# M8650D_cpld.net
KiCad netlist of a schematic drawn in EAGLE
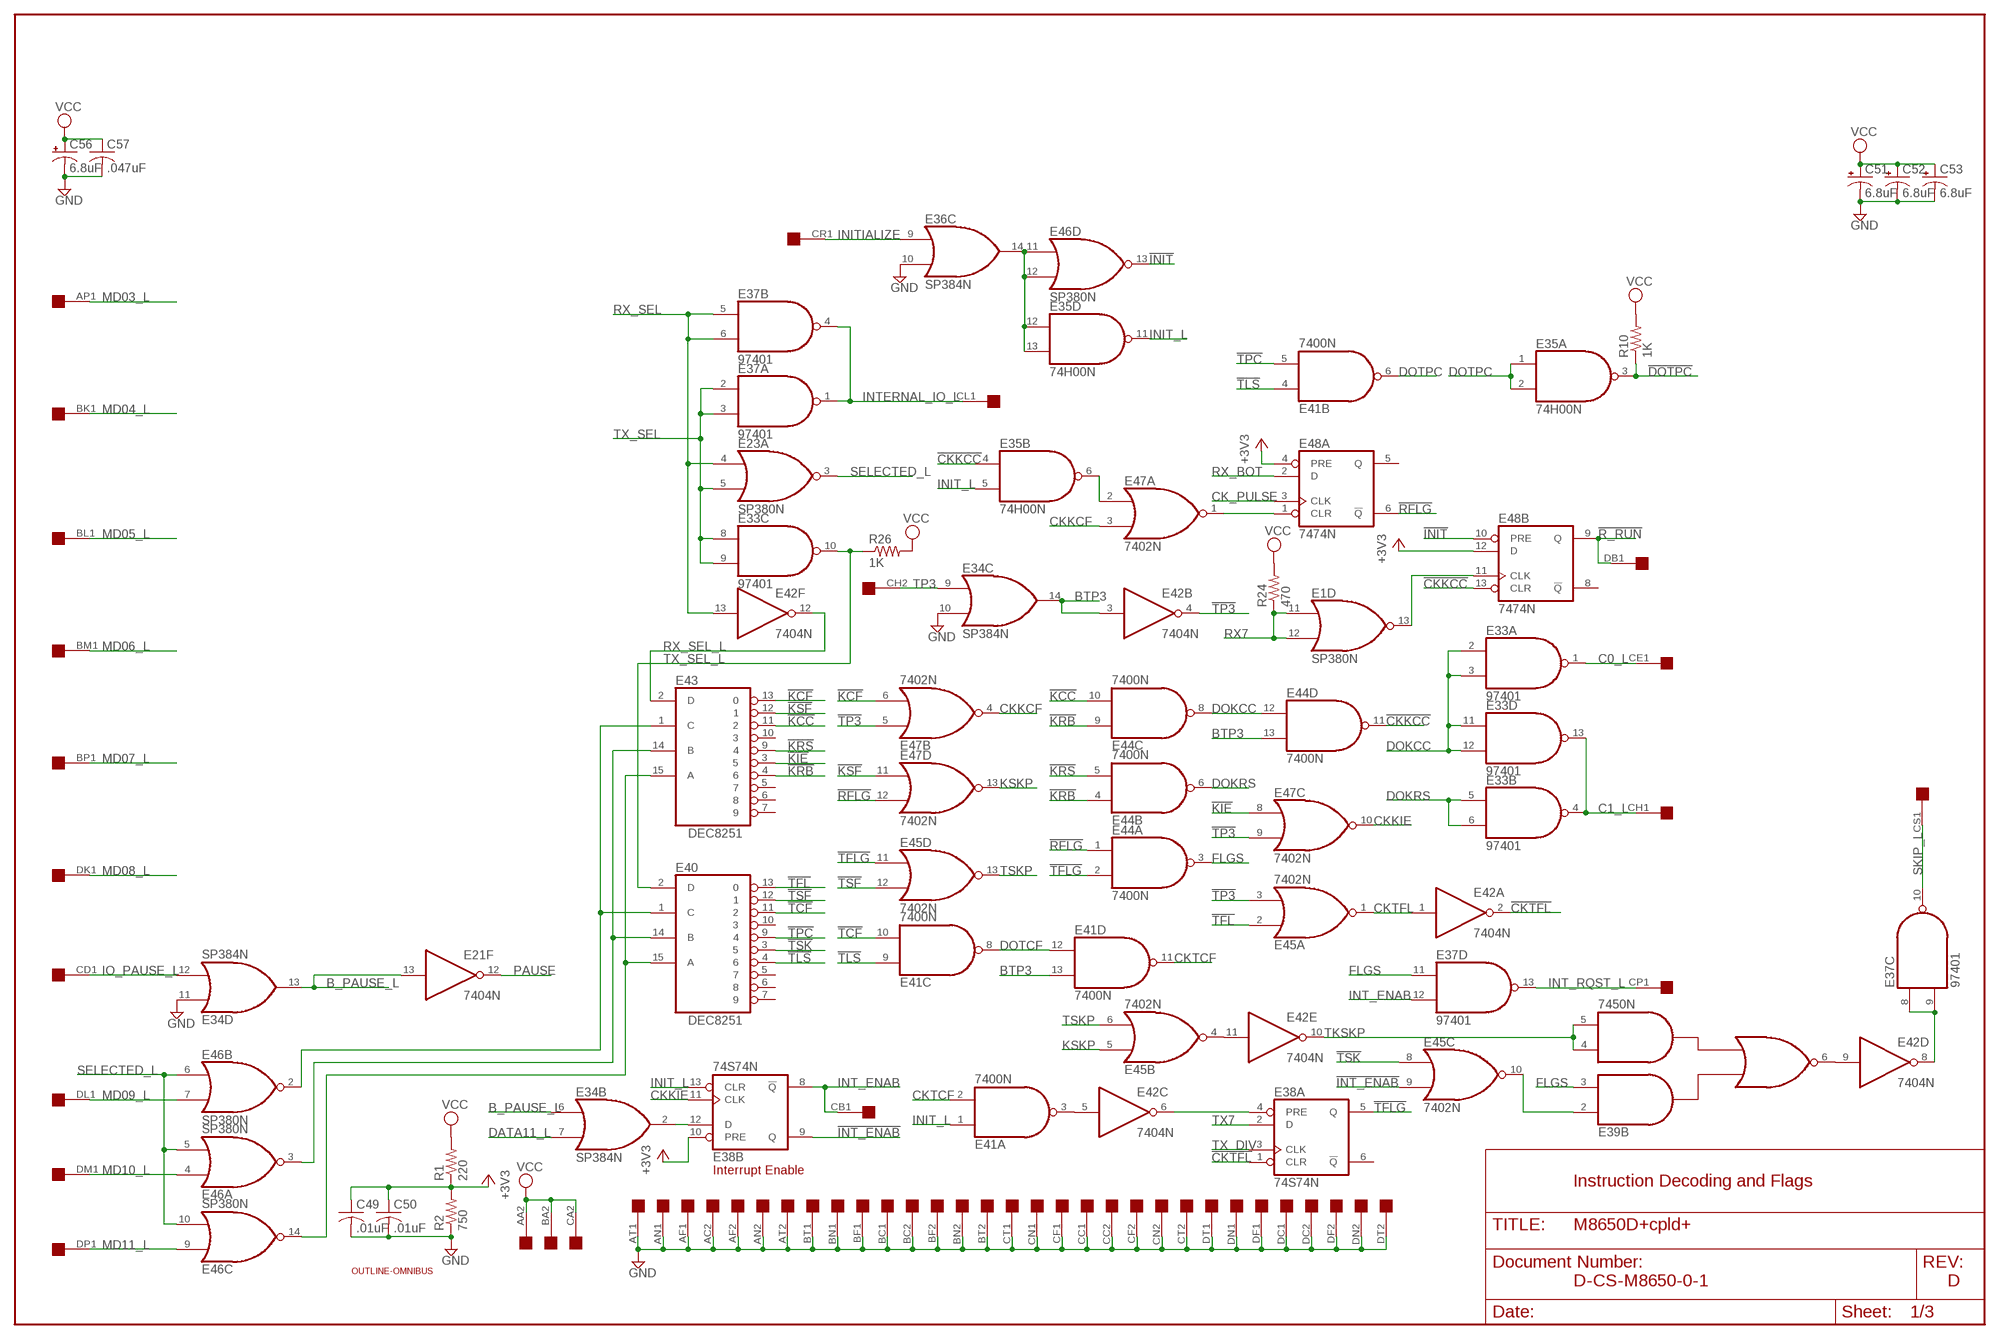
[diagram p0: schematic, sheet 1]
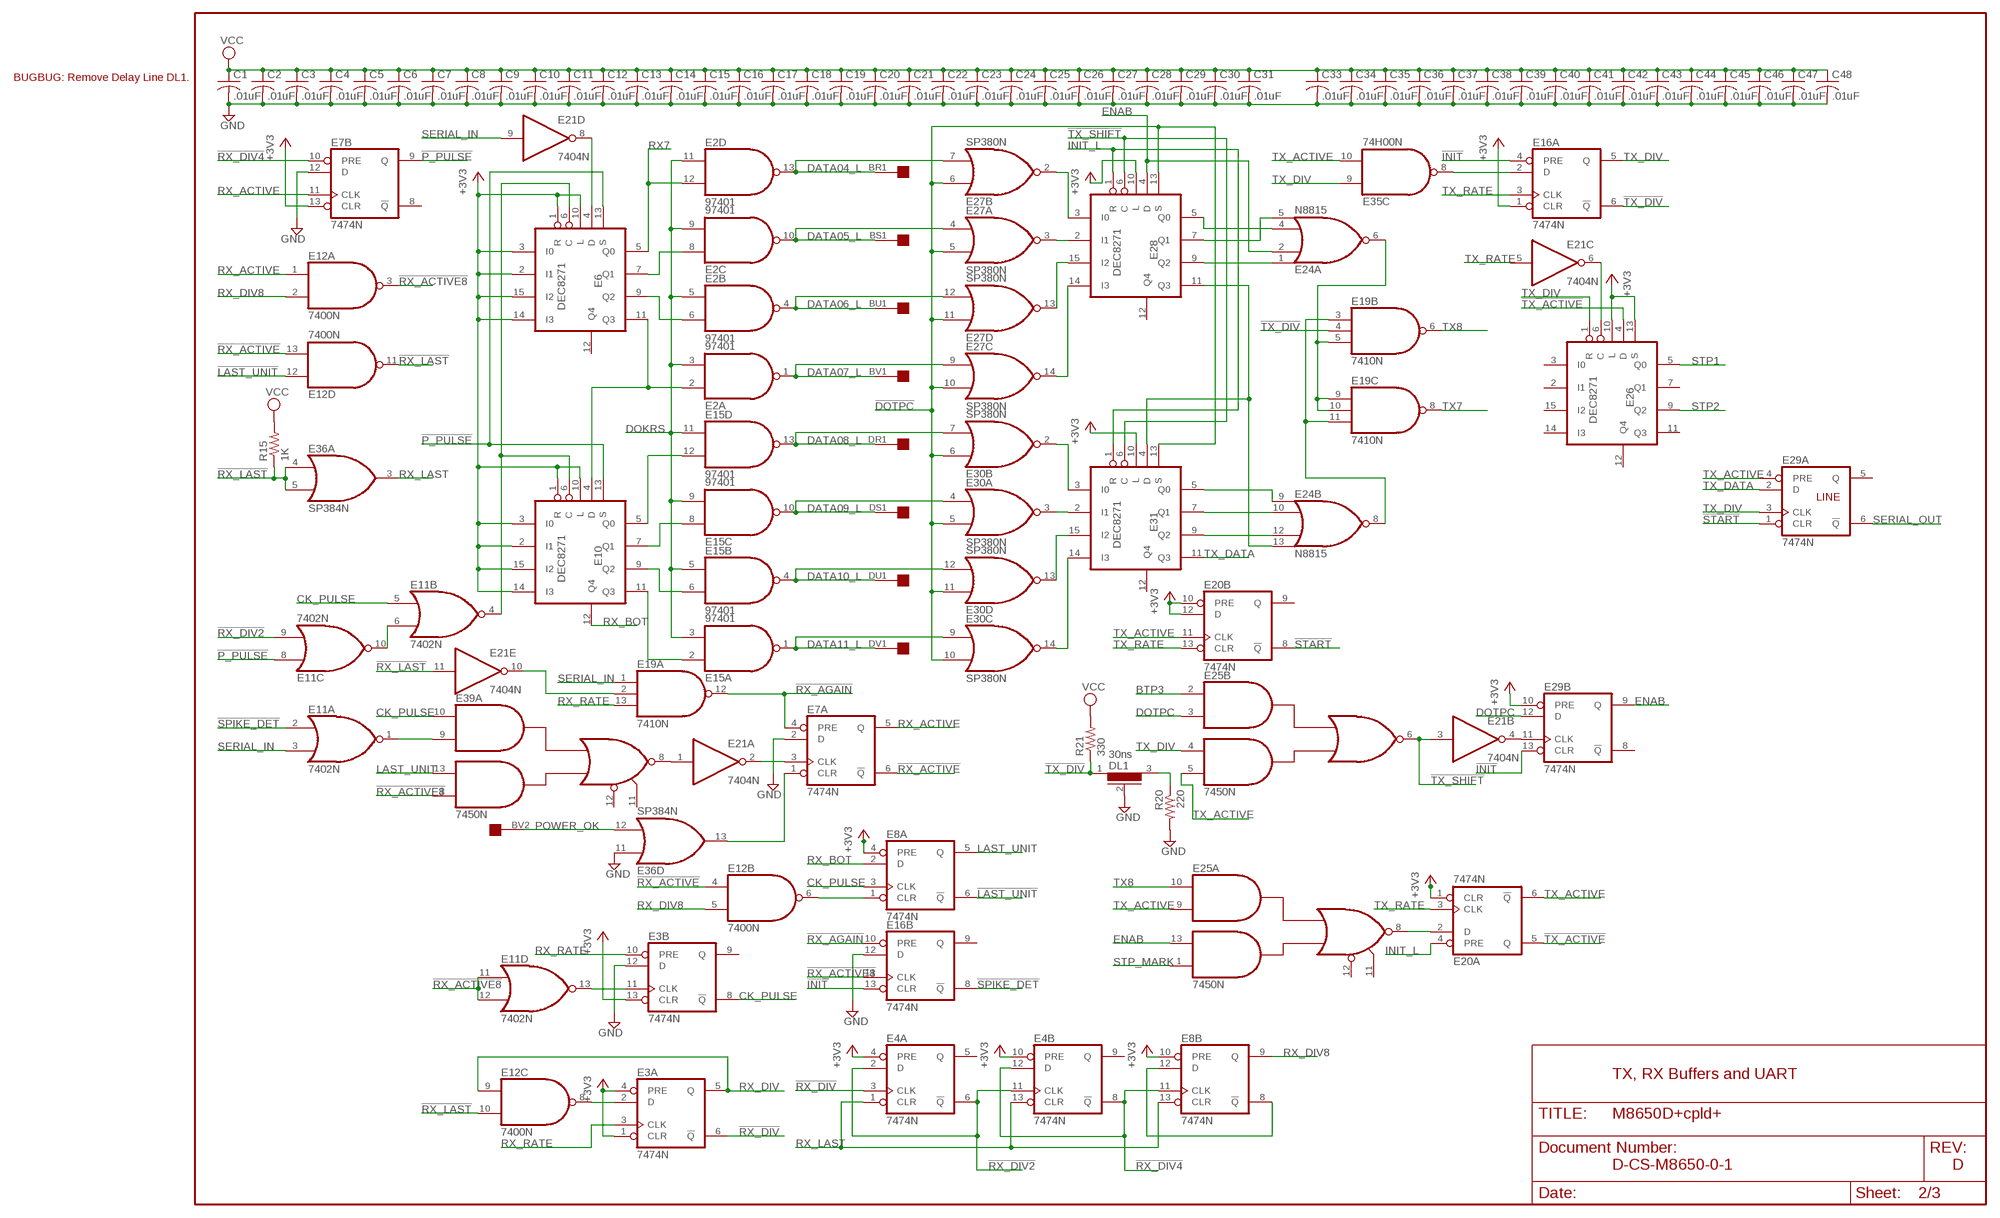
[diagram p1: schematic, sheet 2]
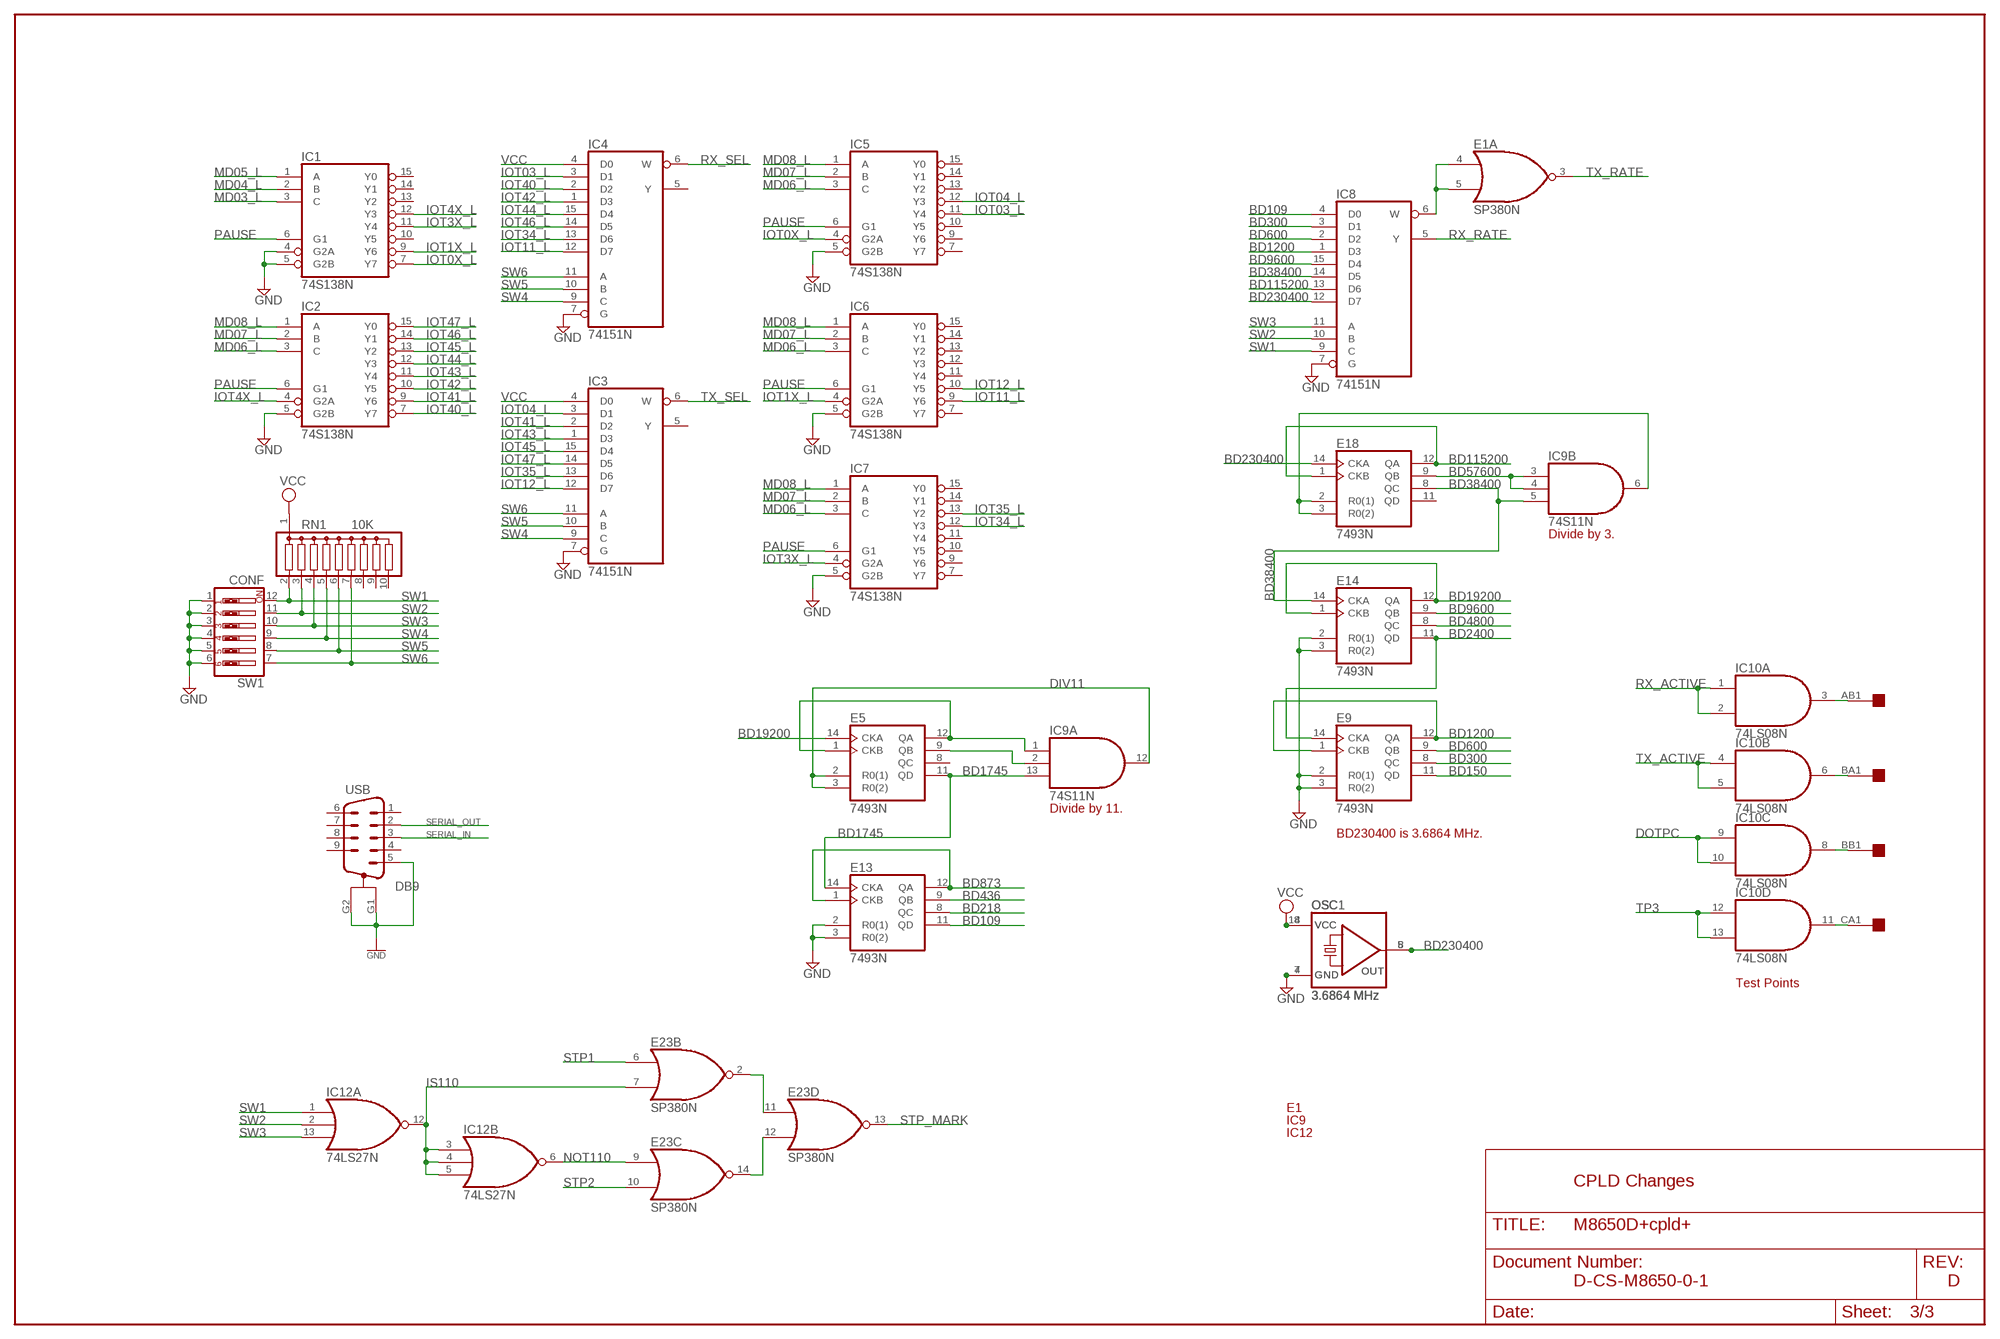
[diagram p2: schematic, sheet 3]

(export (version "E")
  (design (tool "Eeschema 10.0.6"))
  (components
    (comp (ref "E1")
      (value "SP380N")
      (footprint "eagle-import:DIL14")
      (libsource (lib "eagle-import") (part "SP380N"))
    )
    (comp (ref "E5")
      (value "7493N")
      (footprint "eagle-import:DIL14")
      (libsource (lib "eagle-import") (part "7493NLS"))
    )
    (comp (ref "E9")
      (value "7493N")
      (footprint "eagle-import:DIL14")
      (libsource (lib "eagle-import") (part "7493NLS"))
    )
    (comp (ref "E13")
      (value "7493N")
      (footprint "eagle-import:DIL14")
      (libsource (lib "eagle-import") (part "7493NLS"))
    )
    (comp (ref "E14")
      (value "7493N")
      (footprint "eagle-import:DIL14")
      (libsource (lib "eagle-import") (part "7493NLS"))
    )
    (comp (ref "E18")
      (value "7493N")
      (footprint "eagle-import:DIL14")
      (libsource (lib "eagle-import") (part "7493NLS"))
    )
    (comp (ref "E23")
      (value "SP380N")
      (footprint "eagle-import:DIL14")
      (libsource (lib "eagle-import") (part "SP380N"))
    )
    (comp (ref "IC1")
      (value "74S138N")
      (footprint "eagle-import:DIL16")
      (libsource (lib "eagle-import") (part "74138NS"))
    )
    (comp (ref "IC2")
      (value "74S138N")
      (footprint "eagle-import:DIL16")
      (libsource (lib "eagle-import") (part "74138NS"))
    )
    (comp (ref "IC3")
      (value "74151N")
      (footprint "eagle-import:DIL16")
      (libsource (lib "eagle-import") (part "74151NS"))
    )
    (comp (ref "IC4")
      (value "74151N")
      (footprint "eagle-import:DIL16")
      (libsource (lib "eagle-import") (part "74151NS"))
    )
    (comp (ref "IC5")
      (value "74S138N")
      (footprint "eagle-import:DIL16")
      (libsource (lib "eagle-import") (part "74138NS"))
    )
    (comp (ref "IC6")
      (value "74S138N")
      (footprint "eagle-import:DIL16")
      (libsource (lib "eagle-import") (part "74138NS"))
    )
    (comp (ref "IC7")
      (value "74S138N")
      (footprint "eagle-import:DIL16")
      (libsource (lib "eagle-import") (part "74138NS"))
    )
    (comp (ref "IC8")
      (value "74151N")
      (footprint "eagle-import:DIL16")
      (libsource (lib "eagle-import") (part "74151N"))
    )
    (comp (ref "IC9")
      (value "74S11N")
      (footprint "eagle-import:DIL14")
      (libsource (lib "eagle-import") (part "7411NS"))
    )
    (comp (ref "IC10")
      (value "74LS08N")
      (footprint "eagle-import:DIL14")
      (libsource (lib "eagle-import") (part "7408NLS"))
    )
    (comp (ref "IC12")
      (value "74LS27N")
      (footprint "eagle-import:DIL14")
      (libsource (lib "eagle-import") (part "7427NLS"))
    )
    (comp (ref "OSC")
      (value "3.6864 MHz")
      (footprint "eagle-import:DIL08S")
      (libsource (lib "eagle-import") (part "QG5460"))
    )
    (comp (ref "OSC1")
      (value "3.6864 MHz")
      (footprint "eagle-import:DIL14S")
      (libsource (lib "eagle-import") (part "QG5860"))
    )
    (comp (ref "RN1")
      (value "10K")
      (footprint "eagle-import:SIL10")
      (libsource (lib "eagle-import") (part "G09R"))
    )
    (comp (ref "SW1")
      (value "CONF")
      (footprint "eagle-import:EDG-06")
      (libsource (lib "eagle-import") (part "SW_DIP-6"))
    )
    (comp (ref "U$2")
      (value "OMNIBUS")
      (footprint "eagle-import:EDGE-CON8")
      (libsource (lib "eagle-import") (part "QUAD"))
    )
    (comp (ref "USB")
      (value "DB9")
      (footprint "eagle-import:AMP_DB-9RA")
      (fields (field (name "MANF") "TE/AMP"))
      (libsource (lib "eagle-import") (part "DB9"))
    )
    (comp (ref "C49")
      (value ".01uF")
      (footprint "eagle-import:C050-025X075")
      (libsource (lib "eagle-import") (part "C-US050-025X075"))
    )
    (comp (ref "C50")
      (value ".01uF")
      (footprint "eagle-import:C050-025X075")
      (libsource (lib "eagle-import") (part "C-US050-025X075"))
    )
    (comp (ref "C51")
      (value "6.8uF")
      (footprint "eagle-import:E12-8")
      (libsource (lib "eagle-import") (part "CPOL-USE20-8AXIAL"))
    )
    (comp (ref "C52")
      (value "6.8uF")
      (footprint "eagle-import:E12-8")
      (libsource (lib "eagle-import") (part "CPOL-USE20-8AXIAL"))
    )
    (comp (ref "C53")
      (value "6.8uF")
      (footprint "eagle-import:E12-8")
      (libsource (lib "eagle-import") (part "CPOL-USE20-8AXIAL"))
    )
    (comp (ref "C56")
      (value "6.8uF")
      (footprint "eagle-import:E12-8")
      (libsource (lib "eagle-import") (part "CPOL-USE20-8AXIAL"))
    )
    (comp (ref "C57")
      (value ".047uF")
      (footprint "eagle-import:C050-025X075")
      (libsource (lib "eagle-import") (part "C-US050-025X075"))
    )
    (comp (ref "E21")
      (value "7404N")
      (footprint "eagle-import:DIL14")
      (libsource (lib "eagle-import") (part "7404N"))
    )
    (comp (ref "E33")
      (value "97401")
      (footprint "eagle-import:DIL14")
      (libsource (lib "eagle-import") (part "7401NLS"))
    )
    (comp (ref "E34")
      (value "SP384N")
      (footprint "eagle-import:DIL14")
      (libsource (lib "eagle-import") (part "SP384N"))
    )
    (comp (ref "E35")
      (value "74H00N")
      (footprint "eagle-import:DIL14")
      (libsource (lib "eagle-import") (part "7400N"))
    )
    (comp (ref "E36")
      (value "SP384N")
      (footprint "eagle-import:DIL14")
      (libsource (lib "eagle-import") (part "SP384N"))
    )
    (comp (ref "E37")
      (value "97401")
      (footprint "eagle-import:DIL14")
      (libsource (lib "eagle-import") (part "7401NLS"))
    )
    (comp (ref "E38")
      (value "74S74N")
      (footprint "eagle-import:DIL14")
      (libsource (lib "eagle-import") (part "7474NS"))
    )
    (comp (ref "E39")
      (value "7450N")
      (footprint "eagle-import:DIL14")
      (libsource (lib "eagle-import") (part "7450N"))
    )
    (comp (ref "E40")
      (value "DEC8251")
      (footprint "eagle-import:DIL16")
      (libsource (lib "eagle-import") (part "DEC8251"))
    )
    (comp (ref "E41")
      (value "7400N")
      (footprint "eagle-import:DIL14")
      (libsource (lib "eagle-import") (part "7400N"))
    )
    (comp (ref "E42")
      (value "7404N")
      (footprint "eagle-import:DIL14")
      (libsource (lib "eagle-import") (part "7404N"))
    )
    (comp (ref "E43")
      (value "DEC8251")
      (footprint "eagle-import:DIL16")
      (libsource (lib "eagle-import") (part "DEC8251"))
    )
    (comp (ref "E44")
      (value "7400N")
      (footprint "eagle-import:DIL14")
      (libsource (lib "eagle-import") (part "7400N"))
    )
    (comp (ref "E45")
      (value "7402N")
      (footprint "eagle-import:DIL14")
      (libsource (lib "eagle-import") (part "7402N"))
    )
    (comp (ref "E46")
      (value "SP380N")
      (footprint "eagle-import:DIL14")
      (libsource (lib "eagle-import") (part "SP380N"))
    )
    (comp (ref "E47")
      (value "7402N")
      (footprint "eagle-import:DIL14")
      (libsource (lib "eagle-import") (part "7402N"))
    )
    (comp (ref "E48")
      (value "7474N")
      (footprint "eagle-import:DIL14")
      (libsource (lib "eagle-import") (part "7474NS"))
    )
    (comp (ref "R1")
      (value "220")
      (footprint "eagle-import:0207_10")
      (libsource (lib "eagle-import") (part "R-US_0207/10"))
    )
    (comp (ref "R2")
      (value "750")
      (footprint "eagle-import:0207_10")
      (libsource (lib "eagle-import") (part "R-US_0207/10"))
    )
    (comp (ref "R10")
      (value "1K")
      (footprint "eagle-import:0207_10")
      (libsource (lib "eagle-import") (part "R-US_0207/10"))
    )
    (comp (ref "R24")
      (value "470")
      (footprint "eagle-import:0207_10")
      (libsource (lib "eagle-import") (part "R-US_0207/10"))
    )
    (comp (ref "R26")
      (value "1K")
      (footprint "eagle-import:0207_10")
      (libsource (lib "eagle-import") (part "R-US_0207/10"))
    )
    (comp (ref "U$1")
      (value "OUTLINE-OMNIBUS")
      (footprint "eagle-import:OMNIBUS")
      (libsource (lib "eagle-import") (part "OUTLINE-OMNIBUS"))
    )
    (comp (ref "C1")
      (value ".01uF")
      (footprint "eagle-import:C050-025X075")
      (libsource (lib "eagle-import") (part "C-US050-025X075"))
    )
    (comp (ref "C2")
      (value ".01uF")
      (footprint "eagle-import:C050-025X075")
      (libsource (lib "eagle-import") (part "C-US050-025X075"))
    )
    (comp (ref "C3")
      (value ".01uF")
      (footprint "eagle-import:C050-025X075")
      (libsource (lib "eagle-import") (part "C-US050-025X075"))
    )
    (comp (ref "C4")
      (value ".01uF")
      (footprint "eagle-import:C050-025X075")
      (libsource (lib "eagle-import") (part "C-US050-025X075"))
    )
    (comp (ref "C5")
      (value ".01uF")
      (footprint "eagle-import:C050-025X075")
      (libsource (lib "eagle-import") (part "C-US050-025X075"))
    )
    (comp (ref "C6")
      (value ".01uF")
      (footprint "eagle-import:C050-025X075")
      (libsource (lib "eagle-import") (part "C-US050-025X075"))
    )
    (comp (ref "C7")
      (value ".01uF")
      (footprint "eagle-import:C050-025X075")
      (libsource (lib "eagle-import") (part "C-US050-025X075"))
    )
    (comp (ref "C8")
      (value ".01uF")
      (footprint "eagle-import:C050-025X075")
      (libsource (lib "eagle-import") (part "C-US050-025X075"))
    )
    (comp (ref "C9")
      (value ".01uF")
      (footprint "eagle-import:C050-025X075")
      (libsource (lib "eagle-import") (part "C-US050-025X075"))
    )
    (comp (ref "C10")
      (value ".01uF")
      (footprint "eagle-import:C050-025X075")
      (libsource (lib "eagle-import") (part "C-US050-025X075"))
    )
    (comp (ref "C11")
      (value ".01uF")
      (footprint "eagle-import:C050-025X075")
      (libsource (lib "eagle-import") (part "C-US050-025X075"))
    )
    (comp (ref "C12")
      (value ".01uF")
      (footprint "eagle-import:C050-025X075")
      (libsource (lib "eagle-import") (part "C-US050-025X075"))
    )
    (comp (ref "C13")
      (value ".01uF")
      (footprint "eagle-import:C050-025X075")
      (libsource (lib "eagle-import") (part "C-US050-025X075"))
    )
    (comp (ref "C14")
      (value ".01uF")
      (footprint "eagle-import:C050-025X075")
      (libsource (lib "eagle-import") (part "C-US050-025X075"))
    )
    (comp (ref "C15")
      (value ".01uF")
      (footprint "eagle-import:C050-025X075")
      (libsource (lib "eagle-import") (part "C-US050-025X075"))
    )
    (comp (ref "C16")
      (value ".01uF")
      (footprint "eagle-import:C050-025X075")
      (libsource (lib "eagle-import") (part "C-US050-025X075"))
    )
    (comp (ref "C17")
      (value ".01uF")
      (footprint "eagle-import:C050-025X075")
      (libsource (lib "eagle-import") (part "C-US050-025X075"))
    )
    (comp (ref "C18")
      (value ".01uF")
      (footprint "eagle-import:C050-025X075")
      (libsource (lib "eagle-import") (part "C-US050-025X075"))
    )
    (comp (ref "C19")
      (value ".01uF")
      (footprint "eagle-import:C050-025X075")
      (libsource (lib "eagle-import") (part "C-US050-025X075"))
    )
    (comp (ref "C20")
      (value ".01uF")
      (footprint "eagle-import:C050-025X075")
      (libsource (lib "eagle-import") (part "C-US050-025X075"))
    )
    (comp (ref "C21")
      (value ".01uF")
      (footprint "eagle-import:C050-025X075")
      (libsource (lib "eagle-import") (part "C-US050-025X075"))
    )
    (comp (ref "C22")
      (value ".01uF")
      (footprint "eagle-import:C050-025X075")
      (libsource (lib "eagle-import") (part "C-US050-025X075"))
    )
    (comp (ref "C23")
      (value ".01uF")
      (footprint "eagle-import:C050-025X075")
      (libsource (lib "eagle-import") (part "C-US050-025X075"))
    )
    (comp (ref "C24")
      (value ".01uF")
      (footprint "eagle-import:C050-025X075")
      (libsource (lib "eagle-import") (part "C-US050-025X075"))
    )
    (comp (ref "C25")
      (value ".01uF")
      (footprint "eagle-import:C050-025X075")
      (libsource (lib "eagle-import") (part "C-US050-025X075"))
    )
    (comp (ref "C26")
      (value ".01uF")
      (footprint "eagle-import:C050-025X075")
      (libsource (lib "eagle-import") (part "C-US050-025X075"))
    )
    (comp (ref "C27")
      (value ".01uF")
      (footprint "eagle-import:C050-025X075")
      (libsource (lib "eagle-import") (part "C-US050-025X075"))
    )
    (comp (ref "C28")
      (value ".01uF")
      (footprint "eagle-import:C050-025X075")
      (libsource (lib "eagle-import") (part "C-US050-025X075"))
    )
    (comp (ref "C29")
      (value ".01uF")
      (footprint "eagle-import:C050-025X075")
      (libsource (lib "eagle-import") (part "C-US050-025X075"))
    )
    (comp (ref "C30")
      (value ".01uF")
      (footprint "eagle-import:C050-025X075")
      (libsource (lib "eagle-import") (part "C-US050-025X075"))
    )
    (comp (ref "C31")
      (value ".01uF")
      (footprint "eagle-import:C050-025X075")
      (libsource (lib "eagle-import") (part "C-US050-025X075"))
    )
    (comp (ref "C33")
      (value ".01uF")
      (footprint "eagle-import:C050-025X075")
      (libsource (lib "eagle-import") (part "C-US050-025X075"))
    )
    (comp (ref "C34")
      (value ".01uF")
      (footprint "eagle-import:C050-025X075")
      (libsource (lib "eagle-import") (part "C-US050-025X075"))
    )
    (comp (ref "C35")
      (value ".01uF")
      (footprint "eagle-import:C050-025X075")
      (libsource (lib "eagle-import") (part "C-US050-025X075"))
    )
    (comp (ref "C36")
      (value ".01uF")
      (footprint "eagle-import:C050-025X075")
      (libsource (lib "eagle-import") (part "C-US050-025X075"))
    )
    (comp (ref "C37")
      (value ".01uF")
      (footprint "eagle-import:C050-025X075")
      (libsource (lib "eagle-import") (part "C-US050-025X075"))
    )
    (comp (ref "C38")
      (value ".01uF")
      (footprint "eagle-import:C050-025X075")
      (libsource (lib "eagle-import") (part "C-US050-025X075"))
    )
    (comp (ref "C39")
      (value ".01uF")
      (footprint "eagle-import:C050-025X075")
      (libsource (lib "eagle-import") (part "C-US050-025X075"))
    )
    (comp (ref "C40")
      (value ".01uF")
      (footprint "eagle-import:C050-025X075")
      (libsource (lib "eagle-import") (part "C-US050-025X075"))
    )
    (comp (ref "C41")
      (value ".01uF")
      (footprint "eagle-import:C050-025X075")
      (libsource (lib "eagle-import") (part "C-US050-025X075"))
    )
    (comp (ref "C42")
      (value ".01uF")
      (footprint "eagle-import:C050-025X075")
      (libsource (lib "eagle-import") (part "C-US050-025X075"))
    )
    (comp (ref "C43")
      (value ".01uF")
      (footprint "eagle-import:C050-025X075")
      (libsource (lib "eagle-import") (part "C-US050-025X075"))
    )
    (comp (ref "C44")
      (value ".01uF")
      (footprint "eagle-import:C050-025X075")
      (libsource (lib "eagle-import") (part "C-US050-025X075"))
    )
    (comp (ref "C45")
      (value ".01uF")
      (footprint "eagle-import:C050-025X075")
      (libsource (lib "eagle-import") (part "C-US050-025X075"))
    )
    (comp (ref "C46")
      (value ".01uF")
      (footprint "eagle-import:C050-025X075")
      (libsource (lib "eagle-import") (part "C-US050-025X075"))
    )
    (comp (ref "C47")
      (value ".01uF")
      (footprint "eagle-import:C050-025X075")
      (libsource (lib "eagle-import") (part "C-US050-025X075"))
    )
    (comp (ref "C48")
      (value ".01uF")
      (footprint "eagle-import:C050-025X075")
      (libsource (lib "eagle-import") (part "C-US050-025X075"))
    )
    (comp (ref "DL1")
      (value "30ns")
      (footprint "eagle-import:RCL-L-00-05")
      (libsource (lib "eagle-import") (part "RCL-L-00-05"))
    )
    (comp (ref "E2")
      (value "97401")
      (footprint "eagle-import:DIL14")
      (libsource (lib "eagle-import") (part "7401NLS"))
    )
    (comp (ref "E3")
      (value "7474N")
      (footprint "eagle-import:DIL14")
      (libsource (lib "eagle-import") (part "7474NS"))
    )
    (comp (ref "E4")
      (value "7474N")
      (footprint "eagle-import:DIL14")
      (libsource (lib "eagle-import") (part "7474NS"))
    )
    (comp (ref "E6")
      (value "DEC8271")
      (footprint "eagle-import:DIL16")
      (libsource (lib "eagle-import") (part "DEC8271"))
    )
    (comp (ref "E7")
      (value "7474N")
      (footprint "eagle-import:DIL14")
      (libsource (lib "eagle-import") (part "7474NS"))
    )
    (comp (ref "E8")
      (value "7474N")
      (footprint "eagle-import:DIL14")
      (libsource (lib "eagle-import") (part "7474NS"))
    )
    (comp (ref "E10")
      (value "DEC8271")
      (footprint "eagle-import:DIL16")
      (libsource (lib "eagle-import") (part "DEC8271"))
    )
    (comp (ref "E11")
      (value "7402N")
      (footprint "eagle-import:DIL14")
      (libsource (lib "eagle-import") (part "7402N"))
    )
    (comp (ref "E12")
      (value "7400N")
      (footprint "eagle-import:DIL14")
      (libsource (lib "eagle-import") (part "7400N"))
    )
    (comp (ref "E15")
      (value "97401")
      (footprint "eagle-import:DIL14")
      (libsource (lib "eagle-import") (part "7401NLS"))
    )
    (comp (ref "E16")
      (value "7474N")
      (footprint "eagle-import:DIL14")
      (libsource (lib "eagle-import") (part "7474NS"))
    )
    (comp (ref "E19")
      (value "7410N")
      (footprint "eagle-import:DIL14")
      (libsource (lib "eagle-import") (part "7410N"))
    )
    (comp (ref "E20")
      (value "7474N")
      (footprint "eagle-import:DIL14")
      (libsource (lib "eagle-import") (part "7474NS"))
    )
    (comp (ref "E24")
      (value "N8815")
      (footprint "eagle-import:DIL14")
      (libsource (lib "eagle-import") (part "N8815"))
    )
    (comp (ref "E25")
      (value "7450N")
      (footprint "eagle-import:DIL14")
      (libsource (lib "eagle-import") (part "7450N"))
    )
    (comp (ref "E26")
      (value "DEC8271")
      (footprint "eagle-import:DIL16")
      (libsource (lib "eagle-import") (part "DEC8271"))
    )
    (comp (ref "E27")
      (value "SP380N")
      (footprint "eagle-import:DIL14")
      (libsource (lib "eagle-import") (part "SP380N"))
    )
    (comp (ref "E28")
      (value "DEC8271")
      (footprint "eagle-import:DIL16")
      (libsource (lib "eagle-import") (part "DEC8271"))
    )
    (comp (ref "E29")
      (value "7474N")
      (footprint "eagle-import:DIL14")
      (libsource (lib "eagle-import") (part "7474NS"))
    )
    (comp (ref "E30")
      (value "SP380N")
      (footprint "eagle-import:DIL14")
      (libsource (lib "eagle-import") (part "SP380N"))
    )
    (comp (ref "E31")
      (value "DEC8271")
      (footprint "eagle-import:DIL16")
      (libsource (lib "eagle-import") (part "DEC8271"))
    )
    (comp (ref "R15")
      (value "1K")
      (footprint "eagle-import:0207_10")
      (libsource (lib "eagle-import") (part "R-US_0207/10"))
    )
    (comp (ref "R20")
      (value "220")
      (footprint "eagle-import:0207_10")
      (libsource (lib "eagle-import") (part "R-US_0207/10"))
    )
    (comp (ref "R21")
      (value "330")
      (footprint "eagle-import:0207_10")
      (libsource (lib "eagle-import") (part "R-US_0207/10"))
    )
  )
  (nets
    (net (code "1") (name "+3V3") (class "Default")
      (node (ref "C49") (pin "1") (pinfunction "1_1") (pintype "passive"))
      (node (ref "C50") (pin "1") (pinfunction "1_1") (pintype "passive"))
      (node (ref "E10") (pin "1") (pinfunction "R_1") (pintype "input"))
      (node (ref "E10") (pin "10") (pinfunction "L_10") (pintype "input"))
      (node (ref "E10") (pin "14") (pinfunction "I3_14") (pintype "input"))
      (node (ref "E10") (pin "15") (pinfunction "I2_15") (pintype "input"))
      (node (ref "E10") (pin "2") (pinfunction "I1_2") (pintype "input"))
      (node (ref "E10") (pin "3") (pinfunction "I0_3") (pintype "input"))
      (node (ref "E16") (pin "1") (pinfunction "CLR_1") (pintype "input"))
      (node (ref "E20") (pin "1") (pinfunction "CLR_1") (pintype "input"))
      (node (ref "E20") (pin "10") (pinfunction "PRE_10") (pintype "input"))
      (node (ref "E20") (pin "12") (pinfunction "D_12") (pintype "input"))
      (node (ref "E26") (pin "10") (pinfunction "L_10") (pintype "input"))
      (node (ref "E26") (pin "13") (pinfunction "S_13") (pintype "input"))
      (node (ref "E28") (pin "10") (pinfunction "L_10") (pintype "input"))
      (node (ref "E29") (pin "10") (pinfunction "PRE_10") (pintype "input"))
      (node (ref "E3") (pin "1") (pinfunction "CLR_1") (pintype "input"))
      (node (ref "E3") (pin "13") (pinfunction "CLR_13") (pintype "input"))
      (node (ref "E3") (pin "4") (pinfunction "PRE_4") (pintype "input"))
      (node (ref "E31") (pin "10") (pinfunction "L_10") (pintype "input"))
      (node (ref "E38") (pin "10") (pinfunction "PRE_10") (pintype "input"))
      (node (ref "E4") (pin "10") (pinfunction "PRE_10") (pintype "input"))
      (node (ref "E4") (pin "4") (pinfunction "PRE_4") (pintype "input"))
      (node (ref "E48") (pin "12") (pinfunction "D_12") (pintype "input"))
      (node (ref "E48") (pin "4") (pinfunction "PRE_4") (pintype "input"))
      (node (ref "E6") (pin "1") (pinfunction "R_1") (pintype "input"))
      (node (ref "E6") (pin "10") (pinfunction "L_10") (pintype "input"))
      (node (ref "E6") (pin "14") (pinfunction "I3_14") (pintype "input"))
      (node (ref "E6") (pin "15") (pinfunction "I2_15") (pintype "input"))
      (node (ref "E6") (pin "2") (pinfunction "I1_2") (pintype "input"))
      (node (ref "E6") (pin "3") (pinfunction "I0_3") (pintype "input"))
      (node (ref "E7") (pin "13") (pinfunction "CLR_13") (pintype "input"))
      (node (ref "E8") (pin "10") (pinfunction "PRE_10") (pintype "input"))
      (node (ref "E8") (pin "4") (pinfunction "PRE_4") (pintype "input"))
      (node (ref "R1") (pin "1") (pinfunction "1_1") (pintype "passive"))
      (node (ref "R2") (pin "2") (pinfunction "2_2") (pintype "passive"))
    )
    (net (code "2") (name "BD109") (class "Default")
      (node (ref "E13") (pin "11") (pinfunction "QD_11") (pintype "output"))
      (node (ref "IC8") (pin "4") (pinfunction "D0_4") (pintype "input"))
    )
    (net (code "3") (name "BD150") (class "Default")
      (node (ref "E9") (pin "11") (pinfunction "QD_11") (pintype "output"))
    )
    (net (code "4") (name "BD218") (class "Default")
      (node (ref "E13") (pin "8") (pinfunction "QC_8") (pintype "output"))
    )
    (net (code "5") (name "BD300") (class "Default")
      (node (ref "E9") (pin "8") (pinfunction "QC_8") (pintype "output"))
      (node (ref "IC8") (pin "3") (pinfunction "D1_3") (pintype "input"))
    )
    (net (code "6") (name "BD436") (class "Default")
      (node (ref "E13") (pin "9") (pinfunction "QB_9") (pintype "output"))
    )
    (net (code "7") (name "BD600") (class "Default")
      (node (ref "E9") (pin "9") (pinfunction "QB_9") (pintype "output"))
      (node (ref "IC8") (pin "2") (pinfunction "D2_2") (pintype "input"))
    )
    (net (code "8") (name "BD873") (class "Default")
      (node (ref "E13") (pin "1") (pinfunction "CKB_1") (pintype "input"))
      (node (ref "E13") (pin "12") (pinfunction "QA_12") (pintype "output"))
    )
    (net (code "9") (name "BD1200") (class "Default")
      (node (ref "E9") (pin "1") (pinfunction "CKB_1") (pintype "input"))
      (node (ref "E9") (pin "12") (pinfunction "QA_12") (pintype "output"))
      (node (ref "IC8") (pin "1") (pinfunction "D3_1") (pintype "input"))
    )
    (net (code "10") (name "BD1745") (class "Default")
      (node (ref "E13") (pin "14") (pinfunction "CKA_14") (pintype "input"))
      (node (ref "E5") (pin "11") (pinfunction "QD_11") (pintype "output"))
      (node (ref "IC9") (pin "13") (pinfunction "I2_13") (pintype "input"))
    )
    (net (code "11") (name "BD2400") (class "Default")
      (node (ref "E14") (pin "11") (pinfunction "QD_11") (pintype "output"))
      (node (ref "E9") (pin "14") (pinfunction "CKA_14") (pintype "input"))
    )
    (net (code "12") (name "BD4800") (class "Default")
      (node (ref "E14") (pin "8") (pinfunction "QC_8") (pintype "output"))
    )
    (net (code "13") (name "BD9600") (class "Default")
      (node (ref "E14") (pin "9") (pinfunction "QB_9") (pintype "output"))
      (node (ref "IC8") (pin "15") (pinfunction "D4_15") (pintype "input"))
    )
    (net (code "14") (name "BD19200") (class "Default")
      (node (ref "E14") (pin "1") (pinfunction "CKB_1") (pintype "input"))
      (node (ref "E14") (pin "12") (pinfunction "QA_12") (pintype "output"))
      (node (ref "E5") (pin "14") (pinfunction "CKA_14") (pintype "input"))
    )
    (net (code "15") (name "BD38400") (class "Default")
      (node (ref "E14") (pin "14") (pinfunction "CKA_14") (pintype "input"))
      (node (ref "E18") (pin "8") (pinfunction "QC_8") (pintype "output"))
      (node (ref "IC8") (pin "14") (pinfunction "D5_14") (pintype "input"))
      (node (ref "IC9") (pin "5") (pinfunction "I2_5") (pintype "input"))
    )
    (net (code "16") (name "BD57600") (class "Default")
      (node (ref "E18") (pin "9") (pinfunction "QB_9") (pintype "output"))
      (node (ref "IC9") (pin "3") (pinfunction "I0_3") (pintype "input"))
      (node (ref "IC9") (pin "4") (pinfunction "I1_4") (pintype "input"))
    )
    (net (code "17") (name "BD115200") (class "Default")
      (node (ref "E18") (pin "1") (pinfunction "CKB_1") (pintype "input"))
      (node (ref "E18") (pin "12") (pinfunction "QA_12") (pintype "output"))
      (node (ref "IC8") (pin "13") (pinfunction "D6_13") (pintype "input"))
    )
    (net (code "18") (name "BD230400") (class "Default")
      (node (ref "E18") (pin "14") (pinfunction "CKA_14") (pintype "input"))
      (node (ref "IC8") (pin "12") (pinfunction "D7_12") (pintype "input"))
      (node (ref "OSC") (pin "5") (pinfunction "OUT_5") (pintype "output"))
      (node (ref "OSC1") (pin "8") (pinfunction "OUT_8") (pintype "output"))
    )
    (net (code "19") (name "BTP3") (class "Default")
      (node (ref "E25") (pin "2") (pinfunction "I1_2") (pintype "input"))
      (node (ref "E34") (pin "14") (pinfunction "O_14") (pintype "output"))
      (node (ref "E41") (pin "13") (pinfunction "I1_13") (pintype "input"))
      (node (ref "E42") (pin "3") (pinfunction "I_3") (pintype "input"))
      (node (ref "E44") (pin "13") (pinfunction "I1_13") (pintype "input"))
    )
    (net (code "20") (name "B_PAUSE_L") (class "Default")
      (node (ref "E21") (pin "13") (pinfunction "I_13") (pintype "input"))
      (node (ref "E34") (pin "13") (pinfunction "O_13") (pintype "output"))
      (node (ref "E34") (pin "6") (pinfunction "I0_6") (pintype "input"))
    )
    (net (code "21") (name "C0_L") (class "Default")
      (node (ref "E33") (pin "1") (pinfunction "O_1") (pintype "open_collector"))
      (node (ref "U$2") (pin "CE1") (pinfunction "1_CE1") (pintype "bidirectional"))
    )
    (net (code "22") (name "C1_L") (class "Default")
      (node (ref "E33") (pin "13") (pinfunction "O_13") (pintype "open_collector"))
      (node (ref "E33") (pin "4") (pinfunction "O_4") (pintype "open_collector"))
      (node (ref "U$2") (pin "CH1") (pinfunction "1_CH1") (pintype "bidirectional"))
    )
    (net (code "23") (name "CKKCF") (class "Default")
      (node (ref "E47") (pin "3") (pinfunction "I1_3") (pintype "input"))
      (node (ref "E47") (pin "4") (pinfunction "O_4") (pintype "output"))
    )
    (net (code "24") (name "CKKIE") (class "Default")
      (node (ref "E38") (pin "11") (pinfunction "CLK_11") (pintype "input"))
      (node (ref "E47") (pin "10") (pinfunction "O_10") (pintype "output"))
    )
    (net (code "25") (name "CKTCF") (class "Default")
      (node (ref "E41") (pin "11") (pinfunction "O_11") (pintype "output"))
      (node (ref "E41") (pin "2") (pinfunction "I1_2") (pintype "input"))
    )
    (net (code "26") (name "CKTFL") (class "Default")
      (node (ref "E42") (pin "1") (pinfunction "I_1") (pintype "input"))
      (node (ref "E45") (pin "1") (pinfunction "O_1") (pintype "output"))
    )
    (net (code "27") (name "CK_PULSE") (class "Default")
      (node (ref "E11") (pin "5") (pinfunction "I0_5") (pintype "input"))
      (node (ref "E3") (pin "8") (pinfunction "~{Q}_8") (pintype "output"))
      (node (ref "E39") (pin "10") (pinfunction "I1_10") (pintype "input"))
      (node (ref "E48") (pin "3") (pinfunction "CLK_3") (pintype "input"))
      (node (ref "E8") (pin "3") (pinfunction "CLK_3") (pintype "input"))
    )
    (net (code "28") (name "DATA04_L") (class "Default")
      (node (ref "E2") (pin "13") (pinfunction "O_13") (pintype "open_collector"))
      (node (ref "E27") (pin "7") (pinfunction "I1_7") (pintype "input"))
      (node (ref "U$2") (pin "BR1") (pinfunction "1_BR1") (pintype "bidirectional"))
    )
    (net (code "29") (name "DATA05_L") (class "Default")
      (node (ref "E2") (pin "10") (pinfunction "O_10") (pintype "open_collector"))
      (node (ref "E27") (pin "4") (pinfunction "I0_4") (pintype "input"))
      (node (ref "U$2") (pin "BS1") (pinfunction "1_BS1") (pintype "bidirectional"))
    )
    (net (code "30") (name "DATA06_L") (class "Default")
      (node (ref "E2") (pin "4") (pinfunction "O_4") (pintype "open_collector"))
      (node (ref "E27") (pin "12") (pinfunction "I1_12") (pintype "input"))
      (node (ref "U$2") (pin "BU1") (pinfunction "1_BU1") (pintype "bidirectional"))
    )
    (net (code "31") (name "DATA07_L") (class "Default")
      (node (ref "E2") (pin "1") (pinfunction "O_1") (pintype "open_collector"))
      (node (ref "E27") (pin "9") (pinfunction "I0_9") (pintype "input"))
      (node (ref "U$2") (pin "BV1") (pinfunction "1_BV1") (pintype "bidirectional"))
    )
    (net (code "32") (name "DATA08_L") (class "Default")
      (node (ref "E15") (pin "13") (pinfunction "O_13") (pintype "open_collector"))
      (node (ref "E30") (pin "7") (pinfunction "I1_7") (pintype "input"))
      (node (ref "U$2") (pin "DR1") (pinfunction "1_DR1") (pintype "bidirectional"))
    )
    (net (code "33") (name "DATA09_L") (class "Default")
      (node (ref "E15") (pin "10") (pinfunction "O_10") (pintype "open_collector"))
      (node (ref "E30") (pin "4") (pinfunction "I0_4") (pintype "input"))
      (node (ref "U$2") (pin "DS1") (pinfunction "1_DS1") (pintype "bidirectional"))
    )
    (net (code "34") (name "DATA10_L") (class "Default")
      (node (ref "E15") (pin "4") (pinfunction "O_4") (pintype "open_collector"))
      (node (ref "E30") (pin "12") (pinfunction "I1_12") (pintype "input"))
      (node (ref "U$2") (pin "DU1") (pinfunction "1_DU1") (pintype "bidirectional"))
    )
    (net (code "35") (name "DATA11_L") (class "Default")
      (node (ref "E15") (pin "1") (pinfunction "O_1") (pintype "open_collector"))
      (node (ref "E30") (pin "9") (pinfunction "I0_9") (pintype "input"))
      (node (ref "E34") (pin "7") (pinfunction "I1_7") (pintype "input"))
      (node (ref "U$2") (pin "DV1") (pinfunction "1_DV1") (pintype "bidirectional"))
    )
    (net (code "36") (name "DIV11") (class "Default")
      (node (ref "E5") (pin "2") (pinfunction "R0(1)_2") (pintype "input"))
      (node (ref "E5") (pin "3") (pinfunction "R0(2)_3") (pintype "input"))
      (node (ref "IC9") (pin "12") (pinfunction "O_12") (pintype "output"))
    )
    (net (code "37") (name "DOKCC") (class "Default")
      (node (ref "E33") (pin "11") (pinfunction "I0_11") (pintype "input"))
      (node (ref "E33") (pin "12") (pinfunction "I1_12") (pintype "input"))
      (node (ref "E33") (pin "2") (pinfunction "I0_2") (pintype "input"))
      (node (ref "E33") (pin "3") (pinfunction "I1_3") (pintype "input"))
      (node (ref "E44") (pin "12") (pinfunction "I0_12") (pintype "input"))
      (node (ref "E44") (pin "8") (pinfunction "O_8") (pintype "output"))
    )
    (net (code "38") (name "DOKRS") (class "Default")
      (node (ref "E15") (pin "11") (pinfunction "I0_11") (pintype "input"))
      (node (ref "E15") (pin "3") (pinfunction "I1_3") (pintype "input"))
      (node (ref "E15") (pin "5") (pinfunction "I0_5") (pintype "input"))
      (node (ref "E15") (pin "9") (pinfunction "I1_9") (pintype "input"))
      (node (ref "E2") (pin "11") (pinfunction "I0_11") (pintype "input"))
      (node (ref "E2") (pin "3") (pinfunction "I1_3") (pintype "input"))
      (node (ref "E2") (pin "5") (pinfunction "I0_5") (pintype "input"))
      (node (ref "E2") (pin "9") (pinfunction "I1_9") (pintype "input"))
      (node (ref "E33") (pin "5") (pinfunction "I0_5") (pintype "input"))
      (node (ref "E33") (pin "6") (pinfunction "I1_6") (pintype "input"))
      (node (ref "E44") (pin "6") (pinfunction "O_6") (pintype "output"))
    )
    (net (code "39") (name "DOTCF") (class "Default")
      (node (ref "E41") (pin "12") (pinfunction "I0_12") (pintype "input"))
      (node (ref "E41") (pin "8") (pinfunction "O_8") (pintype "output"))
    )
    (net (code "40") (name "DOTPC") (class "Default")
      (node (ref "E25") (pin "3") (pinfunction "I2_3") (pintype "input"))
      (node (ref "E29") (pin "12") (pinfunction "D_12") (pintype "input"))
      (node (ref "E35") (pin "1") (pinfunction "I0_1") (pintype "input"))
      (node (ref "E35") (pin "2") (pinfunction "I1_2") (pintype "input"))
      (node (ref "E41") (pin "6") (pinfunction "O_6") (pintype "output"))
      (node (ref "IC10") (pin "10") (pinfunction "I1_10") (pintype "input"))
      (node (ref "IC10") (pin "9") (pinfunction "I0_9") (pintype "input"))
    )
    (net (code "41") (name "ENAB") (class "Default")
      (node (ref "E24") (pin "2") (pinfunction "I1_2") (pintype "input"))
      (node (ref "E25") (pin "13") (pinfunction "I3_13") (pintype "input"))
      (node (ref "E28") (pin "4") (pinfunction "D_4") (pintype "input"))
      (node (ref "E29") (pin "9") (pinfunction "Q_9") (pintype "output"))
    )
    (net (code "42") (name "FLGS") (class "Default")
      (node (ref "E37") (pin "11") (pinfunction "I0_11") (pintype "input"))
      (node (ref "E39") (pin "3") (pinfunction "I2_3") (pintype "input"))
      (node (ref "E44") (pin "3") (pinfunction "O_3") (pintype "output"))
    )
    (net (code "43") (name "GND") (class "Default")
      (node (ref "C1") (pin "2") (pinfunction "2_2") (pintype "passive"))
      (node (ref "C10") (pin "2") (pinfunction "2_2") (pintype "passive"))
      (node (ref "C11") (pin "2") (pinfunction "2_2") (pintype "passive"))
      (node (ref "C12") (pin "2") (pinfunction "2_2") (pintype "passive"))
      (node (ref "C13") (pin "2") (pinfunction "2_2") (pintype "passive"))
      (node (ref "C14") (pin "2") (pinfunction "2_2") (pintype "passive"))
      (node (ref "C15") (pin "2") (pinfunction "2_2") (pintype "passive"))
      (node (ref "C16") (pin "2") (pinfunction "2_2") (pintype "passive"))
      (node (ref "C17") (pin "2") (pinfunction "2_2") (pintype "passive"))
      (node (ref "C18") (pin "2") (pinfunction "2_2") (pintype "passive"))
      (node (ref "C19") (pin "2") (pinfunction "2_2") (pintype "passive"))
      (node (ref "C2") (pin "2") (pinfunction "2_2") (pintype "passive"))
      (node (ref "C20") (pin "2") (pinfunction "2_2") (pintype "passive"))
      (node (ref "C21") (pin "2") (pinfunction "2_2") (pintype "passive"))
      (node (ref "C22") (pin "2") (pinfunction "2_2") (pintype "passive"))
      (node (ref "C23") (pin "2") (pinfunction "2_2") (pintype "passive"))
      (node (ref "C24") (pin "2") (pinfunction "2_2") (pintype "passive"))
      (node (ref "C25") (pin "2") (pinfunction "2_2") (pintype "passive"))
      (node (ref "C26") (pin "2") (pinfunction "2_2") (pintype "passive"))
      (node (ref "C27") (pin "2") (pinfunction "2_2") (pintype "passive"))
      (node (ref "C28") (pin "2") (pinfunction "2_2") (pintype "passive"))
      (node (ref "C29") (pin "2") (pinfunction "2_2") (pintype "passive"))
      (node (ref "C3") (pin "2") (pinfunction "2_2") (pintype "passive"))
      (node (ref "C30") (pin "2") (pinfunction "2_2") (pintype "passive"))
      (node (ref "C31") (pin "2") (pinfunction "2_2") (pintype "passive"))
      (node (ref "C33") (pin "2") (pinfunction "2_2") (pintype "passive"))
      (node (ref "C34") (pin "2") (pinfunction "2_2") (pintype "passive"))
      (node (ref "C35") (pin "2") (pinfunction "2_2") (pintype "passive"))
      (node (ref "C36") (pin "2") (pinfunction "2_2") (pintype "passive"))
      (node (ref "C37") (pin "2") (pinfunction "2_2") (pintype "passive"))
      (node (ref "C38") (pin "2") (pinfunction "2_2") (pintype "passive"))
      (node (ref "C39") (pin "2") (pinfunction "2_2") (pintype "passive"))
      (node (ref "C4") (pin "2") (pinfunction "2_2") (pintype "passive"))
      (node (ref "C40") (pin "2") (pinfunction "2_2") (pintype "passive"))
      (node (ref "C41") (pin "2") (pinfunction "2_2") (pintype "passive"))
      (node (ref "C42") (pin "2") (pinfunction "2_2") (pintype "passive"))
      (node (ref "C43") (pin "2") (pinfunction "2_2") (pintype "passive"))
      (node (ref "C44") (pin "2") (pinfunction "2_2") (pintype "passive"))
      (node (ref "C45") (pin "2") (pinfunction "2_2") (pintype "passive"))
      (node (ref "C46") (pin "2") (pinfunction "2_2") (pintype "passive"))
      (node (ref "C47") (pin "2") (pinfunction "2_2") (pintype "passive"))
      (node (ref "C48") (pin "2") (pinfunction "2_2") (pintype "passive"))
      (node (ref "C49") (pin "2") (pinfunction "2_2") (pintype "passive"))
      (node (ref "C5") (pin "2") (pinfunction "2_2") (pintype "passive"))
      (node (ref "C50") (pin "2") (pinfunction "2_2") (pintype "passive"))
      (node (ref "C51") (pin "-") (pinfunction "-_-") (pintype "passive"))
      (node (ref "C52") (pin "-") (pinfunction "-_-") (pintype "passive"))
      (node (ref "C53") (pin "-") (pinfunction "-_-") (pintype "passive"))
      (node (ref "C56") (pin "-") (pinfunction "-_-") (pintype "passive"))
      (node (ref "C57") (pin "2") (pinfunction "2_2") (pintype "passive"))
      (node (ref "C6") (pin "2") (pinfunction "2_2") (pintype "passive"))
      (node (ref "C7") (pin "2") (pinfunction "2_2") (pintype "passive"))
      (node (ref "C8") (pin "2") (pinfunction "2_2") (pintype "passive"))
      (node (ref "C9") (pin "2") (pinfunction "2_2") (pintype "passive"))
      (node (ref "DL1") (pin "2") (pinfunction "2_2") (pintype "passive"))
      (node (ref "E13") (pin "2") (pinfunction "R0(1)_2") (pintype "input"))
      (node (ref "E13") (pin "3") (pinfunction "R0(2)_3") (pintype "input"))
      (node (ref "E14") (pin "2") (pinfunction "R0(1)_2") (pintype "input"))
      (node (ref "E14") (pin "3") (pinfunction "R0(2)_3") (pintype "input"))
      (node (ref "E16") (pin "12") (pinfunction "D_12") (pintype "input"))
      (node (ref "E3") (pin "12") (pinfunction "D_12") (pintype "input"))
      (node (ref "E34") (pin "10") (pinfunction "I1_10") (pintype "input"))
      (node (ref "E34") (pin "11") (pinfunction "I0_11") (pintype "input"))
      (node (ref "E36") (pin "10") (pinfunction "I1_10") (pintype "input"))
      (node (ref "E36") (pin "11") (pinfunction "I0_11") (pintype "input"))
      (node (ref "E7") (pin "12") (pinfunction "D_12") (pintype "input"))
      (node (ref "E7") (pin "2") (pinfunction "D_2") (pintype "input"))
      (node (ref "E9") (pin "2") (pinfunction "R0(1)_2") (pintype "input"))
      (node (ref "E9") (pin "3") (pinfunction "R0(2)_3") (pintype "input"))
      (node (ref "IC1") (pin "4") (pinfunction "G2A_4") (pintype "input"))
      (node (ref "IC1") (pin "5") (pinfunction "G2B_5") (pintype "input"))
      (node (ref "IC2") (pin "5") (pinfunction "G2B_5") (pintype "input"))
      (node (ref "IC3") (pin "7") (pinfunction "G_7") (pintype "input"))
      (node (ref "IC4") (pin "7") (pinfunction "G_7") (pintype "input"))
      (node (ref "IC5") (pin "5") (pinfunction "G2B_5") (pintype "input"))
      (node (ref "IC6") (pin "5") (pinfunction "G2B_5") (pintype "input"))
      (node (ref "IC7") (pin "5") (pinfunction "G2B_5") (pintype "input"))
      (node (ref "IC8") (pin "7") (pinfunction "G_7") (pintype "input"))
      (node (ref "OSC") (pin "4") (pinfunction "GND_4") (pintype "power_in"))
      (node (ref "OSC1") (pin "7") (pinfunction "GND_7") (pintype "power_in"))
      (node (ref "R2") (pin "1") (pinfunction "1_1") (pintype "passive"))
      (node (ref "R20") (pin "2") (pinfunction "2_2") (pintype "passive"))
      (node (ref "SW1") (pin "1") (pinfunction "1_1") (pintype "passive"))
      (node (ref "SW1") (pin "2") (pinfunction "2_2") (pintype "passive"))
      (node (ref "SW1") (pin "3") (pinfunction "3_3") (pintype "passive"))
      (node (ref "SW1") (pin "4") (pinfunction "4_4") (pintype "passive"))
      (node (ref "SW1") (pin "5") (pinfunction "5_5") (pintype "passive"))
      (node (ref "SW1") (pin "6") (pinfunction "6_6") (pintype "passive"))
      (node (ref "U$2") (pin "AC2") (pinfunction "1_AC2") (pintype "bidirectional"))
      (node (ref "U$2") (pin "AF1") (pinfunction "1_AF1") (pintype "bidirectional"))
      (node (ref "U$2") (pin "AF2") (pinfunction "1_AF2") (pintype "bidirectional"))
      (node (ref "U$2") (pin "AN1") (pinfunction "1_AN1") (pintype "bidirectional"))
      (node (ref "U$2") (pin "AN2") (pinfunction "1_AN2") (pintype "bidirectional"))
      (node (ref "U$2") (pin "AT1") (pinfunction "1_AT1") (pintype "bidirectional"))
      (node (ref "U$2") (pin "AT2") (pinfunction "1_AT2") (pintype "bidirectional"))
      (node (ref "U$2") (pin "BC1") (pinfunction "1_BC1") (pintype "bidirectional"))
      (node (ref "U$2") (pin "BC2") (pinfunction "1_BC2") (pintype "bidirectional"))
      (node (ref "U$2") (pin "BF1") (pinfunction "1_BF1") (pintype "bidirectional"))
      (node (ref "U$2") (pin "BF2") (pinfunction "1_BF2") (pintype "bidirectional"))
      (node (ref "U$2") (pin "BN1") (pinfunction "1_BN1") (pintype "bidirectional"))
      (node (ref "U$2") (pin "BN2") (pinfunction "1_BN2") (pintype "bidirectional"))
      (node (ref "U$2") (pin "BT1") (pinfunction "1_BT1") (pintype "bidirectional"))
      (node (ref "U$2") (pin "BT2") (pinfunction "1_BT2") (pintype "bidirectional"))
      (node (ref "U$2") (pin "CC1") (pinfunction "1_CC1") (pintype "bidirectional"))
      (node (ref "U$2") (pin "CC2") (pinfunction "1_CC2") (pintype "bidirectional"))
      (node (ref "U$2") (pin "CF1") (pinfunction "1_CF1") (pintype "bidirectional"))
      (node (ref "U$2") (pin "CF2") (pinfunction "1_CF2") (pintype "bidirectional"))
      (node (ref "U$2") (pin "CN1") (pinfunction "1_CN1") (pintype "bidirectional"))
      (node (ref "U$2") (pin "CN2") (pinfunction "1_CN2") (pintype "bidirectional"))
      (node (ref "U$2") (pin "CT1") (pinfunction "1_CT1") (pintype "bidirectional"))
      (node (ref "U$2") (pin "CT2") (pinfunction "1_CT2") (pintype "bidirectional"))
      (node (ref "U$2") (pin "DC1") (pinfunction "1_DC1") (pintype "bidirectional"))
      (node (ref "U$2") (pin "DC2") (pinfunction "1_DC2") (pintype "bidirectional"))
      (node (ref "U$2") (pin "DF1") (pinfunction "1_DF1") (pintype "bidirectional"))
      (node (ref "U$2") (pin "DF2") (pinfunction "1_DF2") (pintype "bidirectional"))
      (node (ref "U$2") (pin "DN1") (pinfunction "1_DN1") (pintype "bidirectional"))
      (node (ref "U$2") (pin "DN2") (pinfunction "1_DN2") (pintype "bidirectional"))
      (node (ref "U$2") (pin "DT1") (pinfunction "1_DT1") (pintype "bidirectional"))
      (node (ref "U$2") (pin "DT2") (pinfunction "1_DT2") (pintype "bidirectional"))
      (node (ref "USB") (pin "5") (pinfunction "5_5") (pintype "passive"))
      (node (ref "USB") (pin "G1") (pinfunction "G1_G1") (pintype "passive"))
      (node (ref "USB") (pin "G2") (pinfunction "G2_G2") (pintype "passive"))
    )
    (net (code "44") (name "INITIALIZE") (class "Default")
      (node (ref "E36") (pin "9") (pinfunction "I0_9") (pintype "input"))
      (node (ref "U$2") (pin "CR1") (pinfunction "1_CR1") (pintype "bidirectional"))
    )
    (net (code "45") (name "INIT_L") (class "Default")
      (node (ref "E20") (pin "4") (pinfunction "PRE_4") (pintype "input"))
      (node (ref "E28") (pin "1") (pinfunction "R_1") (pintype "input"))
      (node (ref "E31") (pin "1") (pinfunction "R_1") (pintype "input"))
      (node (ref "E35") (pin "11") (pinfunction "O_11") (pintype "output"))
      (node (ref "E35") (pin "5") (pinfunction "I1_5") (pintype "input"))
      (node (ref "E38") (pin "13") (pinfunction "CLR_13") (pintype "input"))
      (node (ref "E41") (pin "1") (pinfunction "I0_1") (pintype "input"))
    )
    (net (code "46") (name "INTERNAL_IO_L") (class "Default")
      (node (ref "E37") (pin "1") (pinfunction "O_1") (pintype "open_collector"))
      (node (ref "E37") (pin "4") (pinfunction "O_4") (pintype "open_collector"))
      (node (ref "U$2") (pin "CL1") (pinfunction "1_CL1") (pintype "bidirectional"))
    )
    (net (code "47") (name "INT_ENAB") (class "Default")
      (node (ref "E37") (pin "12") (pinfunction "I1_12") (pintype "input"))
      (node (ref "E38") (pin "8") (pinfunction "~{Q}_8") (pintype "output"))
      (node (ref "U$2") (pin "CB1") (pinfunction "1_CB1") (pintype "bidirectional"))
    )
    (net (code "48") (name "INT_RQST_L") (class "Default")
      (node (ref "E37") (pin "13") (pinfunction "O_13") (pintype "open_collector"))
      (node (ref "U$2") (pin "CP1") (pinfunction "1_CP1") (pintype "bidirectional"))
    )
    (net (code "49") (name "IOT0X_L") (class "Default")
      (node (ref "IC1") (pin "7") (pinfunction "Y7_7") (pintype "output"))
      (node (ref "IC5") (pin "4") (pinfunction "G2A_4") (pintype "input"))
    )
    (net (code "50") (name "IOT1X_L") (class "Default")
      (node (ref "IC1") (pin "9") (pinfunction "Y6_9") (pintype "output"))
      (node (ref "IC6") (pin "4") (pinfunction "G2A_4") (pintype "input"))
    )
    (net (code "51") (name "IOT3X_L") (class "Default")
      (node (ref "IC1") (pin "11") (pinfunction "Y4_11") (pintype "output"))
      (node (ref "IC7") (pin "4") (pinfunction "G2A_4") (pintype "input"))
    )
    (net (code "52") (name "IOT03_L") (class "Default")
      (node (ref "IC4") (pin "3") (pinfunction "D1_3") (pintype "input"))
      (node (ref "IC5") (pin "11") (pinfunction "Y4_11") (pintype "output"))
    )
    (net (code "53") (name "IOT4X_L") (class "Default")
      (node (ref "IC1") (pin "12") (pinfunction "Y3_12") (pintype "output"))
      (node (ref "IC2") (pin "4") (pinfunction "G2A_4") (pintype "input"))
    )
    (net (code "54") (name "IOT04_L") (class "Default")
      (node (ref "IC3") (pin "3") (pinfunction "D1_3") (pintype "input"))
      (node (ref "IC5") (pin "12") (pinfunction "Y3_12") (pintype "output"))
    )
    (net (code "55") (name "IOT11_L") (class "Default")
      (node (ref "IC4") (pin "12") (pinfunction "D7_12") (pintype "input"))
      (node (ref "IC6") (pin "9") (pinfunction "Y6_9") (pintype "output"))
    )
    (net (code "56") (name "IOT12_L") (class "Default")
      (node (ref "IC3") (pin "12") (pinfunction "D7_12") (pintype "input"))
      (node (ref "IC6") (pin "10") (pinfunction "Y5_10") (pintype "output"))
    )
    (net (code "57") (name "IOT34_L") (class "Default")
      (node (ref "IC4") (pin "13") (pinfunction "D6_13") (pintype "input"))
      (node (ref "IC7") (pin "12") (pinfunction "Y3_12") (pintype "output"))
    )
    (net (code "58") (name "IOT35_L") (class "Default")
      (node (ref "IC3") (pin "13") (pinfunction "D6_13") (pintype "input"))
      (node (ref "IC7") (pin "13") (pinfunction "Y2_13") (pintype "output"))
    )
    (net (code "59") (name "IOT40_L") (class "Default")
      (node (ref "IC2") (pin "7") (pinfunction "Y7_7") (pintype "output"))
      (node (ref "IC4") (pin "2") (pinfunction "D2_2") (pintype "input"))
    )
    (net (code "60") (name "IOT41_L") (class "Default")
      (node (ref "IC2") (pin "9") (pinfunction "Y6_9") (pintype "output"))
      (node (ref "IC3") (pin "2") (pinfunction "D2_2") (pintype "input"))
    )
    (net (code "61") (name "IOT42_L") (class "Default")
      (node (ref "IC2") (pin "10") (pinfunction "Y5_10") (pintype "output"))
      (node (ref "IC4") (pin "1") (pinfunction "D3_1") (pintype "input"))
    )
    (net (code "62") (name "IOT43_L") (class "Default")
      (node (ref "IC2") (pin "11") (pinfunction "Y4_11") (pintype "output"))
      (node (ref "IC3") (pin "1") (pinfunction "D3_1") (pintype "input"))
    )
    (net (code "63") (name "IOT44_L") (class "Default")
      (node (ref "IC2") (pin "12") (pinfunction "Y3_12") (pintype "output"))
      (node (ref "IC4") (pin "15") (pinfunction "D4_15") (pintype "input"))
    )
    (net (code "64") (name "IOT45_L") (class "Default")
      (node (ref "IC2") (pin "13") (pinfunction "Y2_13") (pintype "output"))
      (node (ref "IC3") (pin "15") (pinfunction "D4_15") (pintype "input"))
    )
    (net (code "65") (name "IOT46_L") (class "Default")
      (node (ref "IC2") (pin "14") (pinfunction "Y1_14") (pintype "output"))
      (node (ref "IC4") (pin "14") (pinfunction "D5_14") (pintype "input"))
    )
    (net (code "66") (name "IOT47_L") (class "Default")
      (node (ref "IC2") (pin "15") (pinfunction "Y0_15") (pintype "output"))
      (node (ref "IC3") (pin "14") (pinfunction "D5_14") (pintype "input"))
    )
    (net (code "67") (name "IO_PAUSE_L") (class "Default")
      (node (ref "E34") (pin "12") (pinfunction "I1_12") (pintype "input"))
      (node (ref "U$2") (pin "CD1") (pinfunction "1_CD1") (pintype "bidirectional"))
    )
    (net (code "68") (name "IS110") (class "Default")
      (node (ref "E23") (pin "7") (pinfunction "I1_7") (pintype "input"))
      (node (ref "IC12") (pin "12") (pinfunction "O_12") (pintype "output"))
      (node (ref "IC12") (pin "3") (pinfunction "I0_3") (pintype "input"))
      (node (ref "IC12") (pin "4") (pinfunction "I1_4") (pintype "input"))
      (node (ref "IC12") (pin "5") (pinfunction "I2_5") (pintype "input"))
    )
    (net (code "69") (name "KSKP") (class "Default")
      (node (ref "E45") (pin "5") (pinfunction "I0_5") (pintype "input"))
      (node (ref "E47") (pin "13") (pinfunction "O_13") (pintype "output"))
    )
    (net (code "70") (name "LAST_UNIT") (class "Default")
      (node (ref "E39") (pin "13") (pinfunction "I3_13") (pintype "input"))
      (node (ref "E8") (pin "5") (pinfunction "Q_5") (pintype "output"))
    )
    (net (code "71") (name "MD03_L") (class "Default")
      (node (ref "IC1") (pin "3") (pinfunction "C_3") (pintype "input"))
      (node (ref "U$2") (pin "AP1") (pinfunction "1_AP1") (pintype "bidirectional"))
    )
    (net (code "72") (name "MD04_L") (class "Default")
      (node (ref "IC1") (pin "2") (pinfunction "B_2") (pintype "input"))
      (node (ref "U$2") (pin "BK1") (pinfunction "1_BK1") (pintype "bidirectional"))
    )
    (net (code "73") (name "MD05_L") (class "Default")
      (node (ref "IC1") (pin "1") (pinfunction "A_1") (pintype "input"))
      (node (ref "U$2") (pin "BL1") (pinfunction "1_BL1") (pintype "bidirectional"))
    )
    (net (code "74") (name "MD06_L") (class "Default")
      (node (ref "IC2") (pin "3") (pinfunction "C_3") (pintype "input"))
      (node (ref "IC5") (pin "3") (pinfunction "C_3") (pintype "input"))
      (node (ref "IC6") (pin "3") (pinfunction "C_3") (pintype "input"))
      (node (ref "IC7") (pin "3") (pinfunction "C_3") (pintype "input"))
      (node (ref "U$2") (pin "BM1") (pinfunction "1_BM1") (pintype "bidirectional"))
    )
    (net (code "75") (name "MD07_L") (class "Default")
      (node (ref "IC2") (pin "2") (pinfunction "B_2") (pintype "input"))
      (node (ref "IC5") (pin "2") (pinfunction "B_2") (pintype "input"))
      (node (ref "IC6") (pin "2") (pinfunction "B_2") (pintype "input"))
      (node (ref "IC7") (pin "2") (pinfunction "B_2") (pintype "input"))
      (node (ref "U$2") (pin "BP1") (pinfunction "1_BP1") (pintype "bidirectional"))
    )
    (net (code "76") (name "MD08_L") (class "Default")
      (node (ref "IC2") (pin "1") (pinfunction "A_1") (pintype "input"))
      (node (ref "IC5") (pin "1") (pinfunction "A_1") (pintype "input"))
      (node (ref "IC6") (pin "1") (pinfunction "A_1") (pintype "input"))
      (node (ref "IC7") (pin "1") (pinfunction "A_1") (pintype "input"))
      (node (ref "U$2") (pin "DK1") (pinfunction "1_DK1") (pintype "bidirectional"))
    )
    (net (code "77") (name "MD09_L") (class "Default")
      (node (ref "E46") (pin "7") (pinfunction "I1_7") (pintype "input"))
      (node (ref "U$2") (pin "DL1") (pinfunction "1_DL1") (pintype "bidirectional"))
    )
    (net (code "78") (name "MD10_L") (class "Default")
      (node (ref "E46") (pin "4") (pinfunction "I0_4") (pintype "input"))
      (node (ref "U$2") (pin "DM1") (pinfunction "1_DM1") (pintype "bidirectional"))
    )
    (net (code "79") (name "MD11_L") (class "Default")
      (node (ref "E46") (pin "9") (pinfunction "I0_9") (pintype "input"))
      (node (ref "U$2") (pin "DP1") (pinfunction "1_DP1") (pintype "bidirectional"))
    )
    (net (code "80") (name "NOT110") (class "Default")
      (node (ref "E23") (pin "9") (pinfunction "I0_9") (pintype "input"))
      (node (ref "IC12") (pin "6") (pinfunction "O_6") (pintype "output"))
    )
    (net (code "81") (name "Net-(DL1-Pad3)") (class "Default")
      (node (ref "DL1") (pin "3") (pinfunction "3_3") (pintype "passive"))
      (node (ref "R20") (pin "1") (pinfunction "1_1") (pintype "passive"))
    )
    (net (code "82") (name "Net-(E1A-I0)") (class "Default")
      (node (ref "E1") (pin "4") (pinfunction "I0_4") (pintype "input"))
      (node (ref "E1") (pin "5") (pinfunction "I1_5") (pintype "input"))
      (node (ref "IC8") (pin "6") (pinfunction "W_6") (pintype "output"))
    )
    (net (code "83") (name "Net-(E1D-O)") (class "Default")
      (node (ref "E1") (pin "13") (pinfunction "O_13") (pintype "output"))
      (node (ref "E48") (pin "11") (pinfunction "CLK_11") (pintype "input"))
    )
    (net (code "84") (name "Net-(E2B-I1)") (class "Default")
      (node (ref "E2") (pin "6") (pinfunction "I1_6") (pintype "input"))
      (node (ref "E6") (pin "9") (pinfunction "Q2_9") (pintype "output"))
    )
    (net (code "85") (name "Net-(E2C-I0)") (class "Default")
      (node (ref "E2") (pin "8") (pinfunction "I0_8") (pintype "input"))
      (node (ref "E6") (pin "7") (pinfunction "Q1_7") (pintype "output"))
    )
    (net (code "86") (name "Net-(E5A-CKB)") (class "Default")
      (node (ref "E5") (pin "1") (pinfunction "CKB_1") (pintype "input"))
      (node (ref "E5") (pin "12") (pinfunction "QA_12") (pintype "output"))
      (node (ref "IC9") (pin "1") (pinfunction "I0_1") (pintype "input"))
    )
    (net (code "87") (name "Net-(E5A-QB)") (class "Default")
      (node (ref "E5") (pin "9") (pinfunction "QB_9") (pintype "output"))
      (node (ref "IC9") (pin "2") (pinfunction "I1_2") (pintype "input"))
    )
    (net (code "88") (name "Net-(E8B-D)") (class "Default")
      (node (ref "E8") (pin "12") (pinfunction "D_12") (pintype "input"))
      (node (ref "E8") (pin "8") (pinfunction "~{Q}_8") (pintype "output"))
    )
    (net (code "89") (name "Net-(E10A-C)") (class "Default")
      (node (ref "E10") (pin "6") (pinfunction "C_6") (pintype "input"))
      (node (ref "E11") (pin "4") (pinfunction "O_4") (pintype "output"))
      (node (ref "E6") (pin "6") (pinfunction "C_6") (pintype "input"))
    )
    (net (code "90") (name "Net-(E10A-D)") (class "Default")
      (node (ref "E10") (pin "4") (pinfunction "D_4") (pintype "input"))
      (node (ref "E2") (pin "2") (pinfunction "I0_2") (pintype "input"))
      (node (ref "E6") (pin "11") (pinfunction "Q3_11") (pintype "output"))
    )
    (net (code "91") (name "Net-(E10A-Q0)") (class "Default")
      (node (ref "E10") (pin "5") (pinfunction "Q0_5") (pintype "output"))
      (node (ref "E15") (pin "12") (pinfunction "I1_12") (pintype "input"))
    )
    (net (code "92") (name "Net-(E10A-Q1)") (class "Default")
      (node (ref "E10") (pin "7") (pinfunction "Q1_7") (pintype "output"))
      (node (ref "E15") (pin "8") (pinfunction "I0_8") (pintype "input"))
    )
    (net (code "93") (name "Net-(E10A-Q2)") (class "Default")
      (node (ref "E10") (pin "9") (pinfunction "Q2_9") (pintype "output"))
      (node (ref "E15") (pin "6") (pinfunction "I1_6") (pintype "input"))
    )
    (net (code "94") (name "Net-(E10A-Q3)") (class "Default")
      (node (ref "E10") (pin "11") (pinfunction "Q3_11") (pintype "output"))
      (node (ref "E15") (pin "2") (pinfunction "I0_2") (pintype "input"))
    )
    (net (code "95") (name "Net-(E11A-O)") (class "Default")
      (node (ref "E11") (pin "1") (pinfunction "O_1") (pintype "output"))
      (node (ref "E39") (pin "9") (pinfunction "I2_9") (pintype "input"))
    )
    (net (code "96") (name "Net-(E11B-I1)") (class "Default")
      (node (ref "E11") (pin "10") (pinfunction "O_10") (pintype "output"))
      (node (ref "E11") (pin "6") (pinfunction "I1_6") (pintype "input"))
    )
    (net (code "97") (name "Net-(E11D-O)") (class "Default")
      (node (ref "E11") (pin "13") (pinfunction "O_13") (pintype "output"))
      (node (ref "E3") (pin "11") (pinfunction "CLK_11") (pintype "input"))
    )
    (net (code "98") (name "Net-(E12B-O)") (class "Default")
      (node (ref "E12") (pin "6") (pinfunction "O_6") (pintype "output"))
      (node (ref "E8") (pin "1") (pinfunction "CLR_1") (pintype "input"))
    )
    (net (code "99") (name "Net-(E12C-O)") (class "Default")
      (node (ref "E12") (pin "8") (pinfunction "O_8") (pintype "output"))
      (node (ref "E3") (pin "2") (pinfunction "D_2") (pintype "input"))
    )
    (net (code "100") (name "Net-(E16A-D)") (class "Default")
      (node (ref "E16") (pin "2") (pinfunction "D_2") (pintype "input"))
      (node (ref "E35") (pin "8") (pinfunction "O_8") (pintype "output"))
    )
    (net (code "101") (name "Net-(E18A-R0(1))") (class "Default")
      (node (ref "E18") (pin "2") (pinfunction "R0(1)_2") (pintype "input"))
      (node (ref "E18") (pin "3") (pinfunction "R0(2)_3") (pintype "input"))
      (node (ref "IC9") (pin "6") (pinfunction "O_6") (pintype "output"))
    )
    (net (code "102") (name "Net-(E19A-I1)") (class "Default")
      (node (ref "E19") (pin "2") (pinfunction "I1_2") (pintype "input"))
      (node (ref "E21") (pin "10") (pinfunction "O_10") (pintype "output"))
    )
    (net (code "103") (name "Net-(E19B-I0)") (class "Default")
      (node (ref "E19") (pin "11") (pinfunction "I2_11") (pintype "input"))
      (node (ref "E19") (pin "3") (pinfunction "I0_3") (pintype "input"))
      (node (ref "E24") (pin "8") (pinfunction "O_8") (pintype "output"))
    )
    (net (code "104") (name "Net-(E19B-I2)") (class "Default")
      (node (ref "E19") (pin "10") (pinfunction "I1_10") (pintype "input"))
      (node (ref "E19") (pin "5") (pinfunction "I2_5") (pintype "input"))
      (node (ref "E19") (pin "9") (pinfunction "I0_9") (pintype "input"))
      (node (ref "E24") (pin "6") (pinfunction "O_6") (pintype "output"))
    )
    (net (code "105") (name "Net-(E20A-D)") (class "Default")
      (node (ref "E20") (pin "2") (pinfunction "D_2") (pintype "input"))
      (node (ref "E25") (pin "8") (pinfunction "O_8") (pintype "output"))
    )
    (net (code "106") (name "Net-(E21A-I)") (class "Default")
      (node (ref "E21") (pin "1") (pinfunction "I_1") (pintype "input"))
      (node (ref "E39") (pin "8") (pinfunction "O_8") (pintype "output"))
    )
    (net (code "107") (name "Net-(E21A-O)") (class "Default")
      (node (ref "E21") (pin "2") (pinfunction "O_2") (pintype "output"))
      (node (ref "E7") (pin "3") (pinfunction "CLK_3") (pintype "input"))
    )
    (net (code "108") (name "Net-(E21B-O)") (class "Default")
      (node (ref "E21") (pin "4") (pinfunction "O_4") (pintype "output"))
      (node (ref "E29") (pin "11") (pinfunction "CLK_11") (pintype "input"))
    )
    (net (code "109") (name "Net-(E21C-O)") (class "Default")
      (node (ref "E21") (pin "6") (pinfunction "O_6") (pintype "output"))
      (node (ref "E26") (pin "6") (pinfunction "C_6") (pintype "input"))
    )
    (net (code "110") (name "Net-(E21D-O)") (class "Default")
      (node (ref "E21") (pin "8") (pinfunction "O_8") (pintype "output"))
      (node (ref "E6") (pin "4") (pinfunction "D_4") (pintype "input"))
    )
    (net (code "111") (name "Net-(E23B-O)") (class "Default")
      (node (ref "E23") (pin "11") (pinfunction "I0_11") (pintype "input"))
      (node (ref "E23") (pin "2") (pinfunction "O_2") (pintype "output"))
    )
    (net (code "112") (name "Net-(E23C-O)") (class "Default")
      (node (ref "E23") (pin "12") (pinfunction "I1_12") (pintype "input"))
      (node (ref "E23") (pin "14") (pinfunction "O_14") (pintype "output"))
    )
    (net (code "113") (name "Net-(E24A-I0)") (class "Default")
      (node (ref "E24") (pin "1") (pinfunction "I0_1") (pintype "input"))
      (node (ref "E28") (pin "9") (pinfunction "Q2_9") (pintype "output"))
    )
    (net (code "114") (name "Net-(E24A-I2)") (class "Default")
      (node (ref "E24") (pin "4") (pinfunction "I2_4") (pintype "input"))
      (node (ref "E28") (pin "5") (pinfunction "Q0_5") (pintype "output"))
    )
    (net (code "115") (name "Net-(E24A-I3)") (class "Default")
      (node (ref "E24") (pin "5") (pinfunction "I3_5") (pintype "input"))
      (node (ref "E28") (pin "7") (pinfunction "Q1_7") (pintype "output"))
    )
    (net (code "116") (name "Net-(E24B-I0)") (class "Default")
      (node (ref "E24") (pin "9") (pinfunction "I0_9") (pintype "input"))
      (node (ref "E31") (pin "5") (pinfunction "Q0_5") (pintype "output"))
    )
    (net (code "117") (name "Net-(E24B-I1)") (class "Default")
      (node (ref "E24") (pin "10") (pinfunction "I1_10") (pintype "input"))
      (node (ref "E31") (pin "7") (pinfunction "Q1_7") (pintype "output"))
    )
    (net (code "118") (name "Net-(E24B-I2)") (class "Default")
      (node (ref "E24") (pin "12") (pinfunction "I2_12") (pintype "input"))
      (node (ref "E31") (pin "9") (pinfunction "Q2_9") (pintype "output"))
    )
    (net (code "119") (name "Net-(E24B-I3)") (class "Default")
      (node (ref "E24") (pin "13") (pinfunction "I3_13") (pintype "input"))
      (node (ref "E28") (pin "11") (pinfunction "Q3_11") (pintype "output"))
      (node (ref "E31") (pin "4") (pinfunction "D_4") (pintype "input"))
    )
    (net (code "120") (name "Net-(E27A-O)") (class "Default")
      (node (ref "E27") (pin "3") (pinfunction "O_3") (pintype "output"))
      (node (ref "E28") (pin "2") (pinfunction "I1_2") (pintype "input"))
    )
    (net (code "121") (name "Net-(E27B-O)") (class "Default")
      (node (ref "E27") (pin "2") (pinfunction "O_2") (pintype "output"))
      (node (ref "E28") (pin "3") (pinfunction "I0_3") (pintype "input"))
    )
    (net (code "122") (name "Net-(E27C-O)") (class "Default")
      (node (ref "E27") (pin "14") (pinfunction "O_14") (pintype "output"))
      (node (ref "E28") (pin "14") (pinfunction "I3_14") (pintype "input"))
    )
    (net (code "123") (name "Net-(E27D-O)") (class "Default")
      (node (ref "E27") (pin "13") (pinfunction "O_13") (pintype "output"))
      (node (ref "E28") (pin "15") (pinfunction "I2_15") (pintype "input"))
    )
    (net (code "124") (name "Net-(E30A-O)") (class "Default")
      (node (ref "E30") (pin "3") (pinfunction "O_3") (pintype "output"))
      (node (ref "E31") (pin "2") (pinfunction "I1_2") (pintype "input"))
    )
    (net (code "125") (name "Net-(E30B-O)") (class "Default")
      (node (ref "E30") (pin "2") (pinfunction "O_2") (pintype "output"))
      (node (ref "E31") (pin "3") (pinfunction "I0_3") (pintype "input"))
    )
    (net (code "126") (name "Net-(E30C-O)") (class "Default")
      (node (ref "E30") (pin "14") (pinfunction "O_14") (pintype "output"))
      (node (ref "E31") (pin "14") (pinfunction "I3_14") (pintype "input"))
    )
    (net (code "127") (name "Net-(E30D-O)") (class "Default")
      (node (ref "E30") (pin "13") (pinfunction "O_13") (pintype "output"))
      (node (ref "E31") (pin "15") (pinfunction "I2_15") (pintype "input"))
    )
    (net (code "128") (name "Net-(E34B-O)") (class "Default")
      (node (ref "E34") (pin "2") (pinfunction "O_2") (pintype "output"))
      (node (ref "E38") (pin "12") (pinfunction "D_12") (pintype "input"))
    )
    (net (code "129") (name "Net-(E35B-O)") (class "Default")
      (node (ref "E35") (pin "6") (pinfunction "O_6") (pintype "output"))
      (node (ref "E47") (pin "2") (pinfunction "I0_2") (pintype "input"))
    )
    (net (code "130") (name "Net-(E35D-I0)") (class "Default")
      (node (ref "E35") (pin "12") (pinfunction "I0_12") (pintype "input"))
      (node (ref "E35") (pin "13") (pinfunction "I1_13") (pintype "input"))
      (node (ref "E36") (pin "14") (pinfunction "O_14") (pintype "output"))
      (node (ref "E46") (pin "11") (pinfunction "I0_11") (pintype "input"))
      (node (ref "E46") (pin "12") (pinfunction "I1_12") (pintype "input"))
    )
    (net (code "131") (name "Net-(E36D-O)") (class "Default")
      (node (ref "E36") (pin "13") (pinfunction "O_13") (pintype "output"))
      (node (ref "E7") (pin "1") (pinfunction "CLR_1") (pintype "input"))
    )
    (net (code "132") (name "Net-(E37C-I0)") (class "Default")
      (node (ref "E37") (pin "8") (pinfunction "I0_8") (pintype "input"))
      (node (ref "E37") (pin "9") (pinfunction "I1_9") (pintype "input"))
      (node (ref "E42") (pin "8") (pinfunction "O_8") (pintype "output"))
    )
    (net (code "133") (name "Net-(E38A-PRE)") (class "Default")
      (node (ref "E38") (pin "4") (pinfunction "PRE_4") (pintype "input"))
      (node (ref "E42") (pin "6") (pinfunction "O_6") (pintype "output"))
    )
    (net (code "134") (name "Net-(E39B-I1)") (class "Default")
      (node (ref "E39") (pin "2") (pinfunction "I1_2") (pintype "input"))
      (node (ref "E45") (pin "10") (pinfunction "O_10") (pintype "output"))
    )
    (net (code "135") (name "Net-(E39B-O)") (class "Default")
      (node (ref "E39") (pin "6") (pinfunction "O_6") (pintype "output"))
      (node (ref "E42") (pin "9") (pinfunction "I_9") (pintype "input"))
    )
    (net (code "136") (name "Net-(E40A-A)") (class "Default")
      (node (ref "E40") (pin "15") (pinfunction "A_15") (pintype "input"))
      (node (ref "E43") (pin "15") (pinfunction "A_15") (pintype "input"))
      (node (ref "E46") (pin "14") (pinfunction "O_14") (pintype "output"))
    )
    (net (code "137") (name "Net-(E40A-B)") (class "Default")
      (node (ref "E40") (pin "14") (pinfunction "B_14") (pintype "input"))
      (node (ref "E43") (pin "14") (pinfunction "B_14") (pintype "input"))
      (node (ref "E46") (pin "3") (pinfunction "O_3") (pintype "output"))
    )
    (net (code "138") (name "Net-(E40A-C)") (class "Default")
      (node (ref "E40") (pin "1") (pinfunction "C_1") (pintype "input"))
      (node (ref "E43") (pin "1") (pinfunction "C_1") (pintype "input"))
      (node (ref "E46") (pin "2") (pinfunction "O_2") (pintype "output"))
    )
    (net (code "139") (name "Net-(E41A-O)") (class "Default")
      (node (ref "E41") (pin "3") (pinfunction "O_3") (pintype "output"))
      (node (ref "E42") (pin "5") (pinfunction "I_5") (pintype "input"))
    )
    (net (code "140") (name "Net-(E42E-I)") (class "Default")
      (node (ref "E42") (pin "11") (pinfunction "I_11") (pintype "input"))
      (node (ref "E45") (pin "4") (pinfunction "O_4") (pintype "output"))
    )
    (net (code "141") (name "Net-(E47A-O)") (class "Default")
      (node (ref "E47") (pin "1") (pinfunction "O_1") (pintype "output"))
      (node (ref "E48") (pin "1") (pinfunction "CLR_1") (pintype "input"))
    )
    (net (code "142") (name "Net-(IC10A-O)") (class "Default")
      (node (ref "IC10") (pin "3") (pinfunction "O_3") (pintype "output"))
      (node (ref "U$2") (pin "AB1") (pinfunction "1_AB1") (pintype "bidirectional"))
    )
    (net (code "143") (name "Net-(IC10B-O)") (class "Default")
      (node (ref "IC10") (pin "6") (pinfunction "O_6") (pintype "output"))
      (node (ref "U$2") (pin "BA1") (pinfunction "1_BA1") (pintype "bidirectional"))
    )
    (net (code "144") (name "Net-(IC10C-O)") (class "Default")
      (node (ref "IC10") (pin "8") (pinfunction "O_8") (pintype "output"))
      (node (ref "U$2") (pin "BB1") (pinfunction "1_BB1") (pintype "bidirectional"))
    )
    (net (code "145") (name "Net-(IC10D-O)") (class "Default")
      (node (ref "IC10") (pin "11") (pinfunction "O_11") (pintype "output"))
      (node (ref "U$2") (pin "CA1") (pinfunction "1_CA1") (pintype "bidirectional"))
    )
    (net (code "146") (name "PAUSE") (class "Default")
      (node (ref "E21") (pin "12") (pinfunction "O_12") (pintype "output"))
      (node (ref "IC1") (pin "6") (pinfunction "G1_6") (pintype "input"))
      (node (ref "IC2") (pin "6") (pinfunction "G1_6") (pintype "input"))
      (node (ref "IC5") (pin "6") (pinfunction "G1_6") (pintype "input"))
      (node (ref "IC6") (pin "6") (pinfunction "G1_6") (pintype "input"))
      (node (ref "IC7") (pin "6") (pinfunction "G1_6") (pintype "input"))
    )
    (net (code "147") (name "POWER_OK") (class "Default")
      (node (ref "E36") (pin "12") (pinfunction "I1_12") (pintype "input"))
      (node (ref "U$2") (pin "BV2") (pinfunction "1_BV2") (pintype "bidirectional"))
    )
    (net (code "148") (name "RX7") (class "Default")
      (node (ref "E1") (pin "11") (pinfunction "I0_11") (pintype "input"))
      (node (ref "E1") (pin "12") (pinfunction "I1_12") (pintype "input"))
      (node (ref "E2") (pin "12") (pinfunction "I1_12") (pintype "input"))
      (node (ref "E6") (pin "5") (pinfunction "Q0_5") (pintype "output"))
      (node (ref "R24") (pin "1") (pinfunction "1_1") (pintype "passive"))
    )
    (net (code "149") (name "RX_ACTIVE") (class "Default")
      (node (ref "E12") (pin "1") (pinfunction "I0_1") (pintype "input"))
      (node (ref "E7") (pin "11") (pinfunction "CLK_11") (pintype "input"))
      (node (ref "E7") (pin "5") (pinfunction "Q_5") (pintype "output"))
      (node (ref "IC10") (pin "1") (pinfunction "I0_1") (pintype "input"))
      (node (ref "IC10") (pin "2") (pinfunction "I1_2") (pintype "input"))
    )
    (net (code "150") (name "RX_BOT") (class "Default")
      (node (ref "E10") (pin "12") (pinfunction "Q4_12") (pintype "output"))
      (node (ref "E48") (pin "2") (pinfunction "D_2") (pintype "input"))
      (node (ref "E8") (pin "2") (pinfunction "D_2") (pintype "input"))
    )
    (net (code "151") (name "RX_DIV") (class "Default")
      (node (ref "E12") (pin "9") (pinfunction "I0_9") (pintype "input"))
      (node (ref "E3") (pin "5") (pinfunction "Q_5") (pintype "output"))
    )
    (net (code "152") (name "RX_DIV8") (class "Default")
      (node (ref "E12") (pin "2") (pinfunction "I1_2") (pintype "input"))
      (node (ref "E12") (pin "5") (pinfunction "I1_5") (pintype "input"))
      (node (ref "E8") (pin "9") (pinfunction "Q_9") (pintype "output"))
    )
    (net (code "153") (name "RX_LAST") (class "Default")
      (node (ref "E36") (pin "3") (pinfunction "O_3") (pintype "output"))
      (node (ref "E4") (pin "1") (pinfunction "CLR_1") (pintype "input"))
      (node (ref "E4") (pin "13") (pinfunction "CLR_13") (pintype "input"))
      (node (ref "E8") (pin "13") (pinfunction "CLR_13") (pintype "input"))
    )
    (net (code "154") (name "RX_RATE") (class "Default")
      (node (ref "E19") (pin "13") (pinfunction "I2_13") (pintype "input"))
      (node (ref "E3") (pin "10") (pinfunction "PRE_10") (pintype "input"))
      (node (ref "E3") (pin "3") (pinfunction "CLK_3") (pintype "input"))
      (node (ref "IC8") (pin "5") (pinfunction "Y_5") (pintype "output"))
    )
    (net (code "155") (name "RX_SEL") (class "Default")
      (node (ref "E23") (pin "4") (pinfunction "I0_4") (pintype "input"))
      (node (ref "E37") (pin "5") (pinfunction "I0_5") (pintype "input"))
      (node (ref "E37") (pin "6") (pinfunction "I1_6") (pintype "input"))
      (node (ref "E42") (pin "13") (pinfunction "I_13") (pintype "input"))
      (node (ref "IC4") (pin "6") (pinfunction "W_6") (pintype "output"))
    )
    (net (code "156") (name "RX_SEL_L") (class "Default")
      (node (ref "E42") (pin "12") (pinfunction "O_12") (pintype "output"))
      (node (ref "E43") (pin "2") (pinfunction "D_2") (pintype "input"))
    )
    (net (code "157") (name "SELECTED_L") (class "Default")
      (node (ref "E23") (pin "3") (pinfunction "O_3") (pintype "output"))
      (node (ref "E46") (pin "10") (pinfunction "I1_10") (pintype "input"))
      (node (ref "E46") (pin "5") (pinfunction "I1_5") (pintype "input"))
      (node (ref "E46") (pin "6") (pinfunction "I0_6") (pintype "input"))
    )
    (net (code "158") (name "SERIAL_IN") (class "Default")
      (node (ref "E11") (pin "3") (pinfunction "I1_3") (pintype "input"))
      (node (ref "E19") (pin "1") (pinfunction "I0_1") (pintype "input"))
      (node (ref "E21") (pin "9") (pinfunction "I_9") (pintype "input"))
      (node (ref "USB") (pin "3") (pinfunction "3_3") (pintype "passive"))
    )
    (net (code "159") (name "SERIAL_OUT") (class "Default")
      (node (ref "E29") (pin "6") (pinfunction "~{Q}_6") (pintype "output"))
      (node (ref "USB") (pin "2") (pinfunction "2_2") (pintype "passive"))
    )
    (net (code "160") (name "SKIP_L") (class "Default")
      (node (ref "E37") (pin "10") (pinfunction "O_10") (pintype "open_collector"))
      (node (ref "U$2") (pin "CS1") (pinfunction "1_CS1") (pintype "bidirectional"))
    )
    (net (code "161") (name "STP1") (class "Default")
      (node (ref "E23") (pin "6") (pinfunction "I0_6") (pintype "input"))
      (node (ref "E26") (pin "5") (pinfunction "Q0_5") (pintype "output"))
    )
    (net (code "162") (name "STP2") (class "Default")
      (node (ref "E23") (pin "10") (pinfunction "I1_10") (pintype "input"))
      (node (ref "E26") (pin "9") (pinfunction "Q2_9") (pintype "output"))
    )
    (net (code "163") (name "STP_MARK") (class "Default")
      (node (ref "E23") (pin "13") (pinfunction "O_13") (pintype "output"))
      (node (ref "E25") (pin "1") (pinfunction "I4_1") (pintype "input"))
    )
    (net (code "164") (name "SW1") (class "Default")
      (node (ref "IC12") (pin "1") (pinfunction "I0_1") (pintype "input"))
      (node (ref "IC8") (pin "9") (pinfunction "C_9") (pintype "input"))
      (node (ref "RN1") (pin "2") (pinfunction "2_2") (pintype "passive"))
      (node (ref "SW1") (pin "12") (pinfunction "12_12") (pintype "passive"))
    )
    (net (code "165") (name "SW2") (class "Default")
      (node (ref "IC12") (pin "2") (pinfunction "I1_2") (pintype "input"))
      (node (ref "IC8") (pin "10") (pinfunction "B_10") (pintype "input"))
      (node (ref "RN1") (pin "3") (pinfunction "3_3") (pintype "passive"))
      (node (ref "SW1") (pin "11") (pinfunction "11_11") (pintype "passive"))
    )
    (net (code "166") (name "SW3") (class "Default")
      (node (ref "IC12") (pin "13") (pinfunction "I2_13") (pintype "input"))
      (node (ref "IC8") (pin "11") (pinfunction "A_11") (pintype "input"))
      (node (ref "RN1") (pin "4") (pinfunction "4_4") (pintype "passive"))
      (node (ref "SW1") (pin "10") (pinfunction "10_10") (pintype "passive"))
    )
    (net (code "167") (name "SW4") (class "Default")
      (node (ref "IC3") (pin "9") (pinfunction "C_9") (pintype "input"))
      (node (ref "IC4") (pin "9") (pinfunction "C_9") (pintype "input"))
      (node (ref "RN1") (pin "5") (pinfunction "5_5") (pintype "passive"))
      (node (ref "SW1") (pin "9") (pinfunction "9_9") (pintype "passive"))
    )
    (net (code "168") (name "SW5") (class "Default")
      (node (ref "IC3") (pin "10") (pinfunction "B_10") (pintype "input"))
      (node (ref "IC4") (pin "10") (pinfunction "B_10") (pintype "input"))
      (node (ref "RN1") (pin "6") (pinfunction "6_6") (pintype "passive"))
      (node (ref "SW1") (pin "8") (pinfunction "8_8") (pintype "passive"))
    )
    (net (code "169") (name "SW6") (class "Default")
      (node (ref "IC3") (pin "11") (pinfunction "A_11") (pintype "input"))
      (node (ref "IC4") (pin "11") (pinfunction "A_11") (pintype "input"))
      (node (ref "RN1") (pin "7") (pinfunction "7_7") (pintype "passive"))
      (node (ref "SW1") (pin "7") (pinfunction "7_7") (pintype "passive"))
    )
    (net (code "170") (name "TKSKP") (class "Default")
      (node (ref "E39") (pin "4") (pinfunction "I3_4") (pintype "input"))
      (node (ref "E39") (pin "5") (pinfunction "I4_5") (pintype "input"))
      (node (ref "E42") (pin "10") (pinfunction "O_10") (pintype "output"))
    )
    (net (code "171") (name "TP3") (class "Default")
      (node (ref "E34") (pin "9") (pinfunction "I0_9") (pintype "input"))
      (node (ref "IC10") (pin "12") (pinfunction "I0_12") (pintype "input"))
      (node (ref "IC10") (pin "13") (pinfunction "I1_13") (pintype "input"))
      (node (ref "U$2") (pin "CH2") (pinfunction "1_CH2") (pintype "bidirectional"))
    )
    (net (code "172") (name "TSKP") (class "Default")
      (node (ref "E45") (pin "13") (pinfunction "O_13") (pintype "output"))
      (node (ref "E45") (pin "6") (pinfunction "I1_6") (pintype "input"))
    )
    (net (code "173") (name "TX7") (class "Default")
      (node (ref "E19") (pin "8") (pinfunction "O_8") (pintype "output"))
      (node (ref "E38") (pin "2") (pinfunction "D_2") (pintype "input"))
    )
    (net (code "174") (name "TX8") (class "Default")
      (node (ref "E19") (pin "6") (pinfunction "O_6") (pintype "output"))
      (node (ref "E25") (pin "10") (pinfunction "I1_10") (pintype "input"))
    )
    (net (code "175") (name "TX_ACTIVE") (class "Default")
      (node (ref "E20") (pin "11") (pinfunction "CLK_11") (pintype "input"))
      (node (ref "E20") (pin "6") (pinfunction "~{Q}_6") (pintype "output"))
      (node (ref "E25") (pin "5") (pinfunction "I4_5") (pintype "input"))
      (node (ref "E25") (pin "9") (pinfunction "I2_9") (pintype "input"))
      (node (ref "E29") (pin "4") (pinfunction "PRE_4") (pintype "input"))
      (node (ref "E35") (pin "10") (pinfunction "I1_10") (pintype "input"))
      (node (ref "IC10") (pin "4") (pinfunction "I0_4") (pintype "input"))
      (node (ref "IC10") (pin "5") (pinfunction "I1_5") (pintype "input"))
    )
    (net (code "176") (name "TX_DATA") (class "Default")
      (node (ref "E29") (pin "2") (pinfunction "D_2") (pintype "input"))
      (node (ref "E31") (pin "11") (pinfunction "Q3_11") (pintype "output"))
    )
    (net (code "177") (name "TX_DIV") (class "Default")
      (node (ref "E16") (pin "5") (pinfunction "Q_5") (pintype "output"))
      (node (ref "E25") (pin "4") (pinfunction "I3_4") (pintype "input"))
      (node (ref "E26") (pin "1") (pinfunction "R_1") (pintype "input"))
      (node (ref "E29") (pin "3") (pinfunction "CLK_3") (pintype "input"))
      (node (ref "E35") (pin "9") (pinfunction "I0_9") (pintype "input"))
      (node (ref "E38") (pin "3") (pinfunction "CLK_3") (pintype "input"))
    )
    (net (code "178") (name "TX_RATE") (class "Default")
      (node (ref "E1") (pin "3") (pinfunction "O_3") (pintype "output"))
      (node (ref "E16") (pin "3") (pinfunction "CLK_3") (pintype "input"))
      (node (ref "E20") (pin "13") (pinfunction "CLR_13") (pintype "input"))
      (node (ref "E20") (pin "3") (pinfunction "CLK_3") (pintype "input"))
      (node (ref "E21") (pin "5") (pinfunction "I_5") (pintype "input"))
    )
    (net (code "179") (name "TX_SEL") (class "Default")
      (node (ref "E23") (pin "5") (pinfunction "I1_5") (pintype "input"))
      (node (ref "E33") (pin "8") (pinfunction "I0_8") (pintype "input"))
      (node (ref "E33") (pin "9") (pinfunction "I1_9") (pintype "input"))
      (node (ref "E37") (pin "2") (pinfunction "I0_2") (pintype "input"))
      (node (ref "E37") (pin "3") (pinfunction "I1_3") (pintype "input"))
      (node (ref "IC3") (pin "6") (pinfunction "W_6") (pintype "output"))
    )
    (net (code "180") (name "TX_SEL_L") (class "Default")
      (node (ref "E33") (pin "10") (pinfunction "O_10") (pintype "open_collector"))
      (node (ref "E40") (pin "2") (pinfunction "D_2") (pintype "input"))
      (node (ref "R26") (pin "1") (pinfunction "1_1") (pintype "passive"))
    )
    (net (code "181") (name "VCC") (class "Default")
      (node (ref "C1") (pin "1") (pinfunction "1_1") (pintype "passive"))
      (node (ref "C10") (pin "1") (pinfunction "1_1") (pintype "passive"))
      (node (ref "C11") (pin "1") (pinfunction "1_1") (pintype "passive"))
      (node (ref "C12") (pin "1") (pinfunction "1_1") (pintype "passive"))
      (node (ref "C13") (pin "1") (pinfunction "1_1") (pintype "passive"))
      (node (ref "C14") (pin "1") (pinfunction "1_1") (pintype "passive"))
      (node (ref "C15") (pin "1") (pinfunction "1_1") (pintype "passive"))
      (node (ref "C16") (pin "1") (pinfunction "1_1") (pintype "passive"))
      (node (ref "C17") (pin "1") (pinfunction "1_1") (pintype "passive"))
      (node (ref "C18") (pin "1") (pinfunction "1_1") (pintype "passive"))
      (node (ref "C19") (pin "1") (pinfunction "1_1") (pintype "passive"))
      (node (ref "C2") (pin "1") (pinfunction "1_1") (pintype "passive"))
      (node (ref "C20") (pin "1") (pinfunction "1_1") (pintype "passive"))
      (node (ref "C21") (pin "1") (pinfunction "1_1") (pintype "passive"))
      (node (ref "C22") (pin "1") (pinfunction "1_1") (pintype "passive"))
      (node (ref "C23") (pin "1") (pinfunction "1_1") (pintype "passive"))
      (node (ref "C24") (pin "1") (pinfunction "1_1") (pintype "passive"))
      (node (ref "C25") (pin "1") (pinfunction "1_1") (pintype "passive"))
      (node (ref "C26") (pin "1") (pinfunction "1_1") (pintype "passive"))
      (node (ref "C27") (pin "1") (pinfunction "1_1") (pintype "passive"))
      (node (ref "C28") (pin "1") (pinfunction "1_1") (pintype "passive"))
      (node (ref "C29") (pin "1") (pinfunction "1_1") (pintype "passive"))
      (node (ref "C3") (pin "1") (pinfunction "1_1") (pintype "passive"))
      (node (ref "C30") (pin "1") (pinfunction "1_1") (pintype "passive"))
      (node (ref "C31") (pin "1") (pinfunction "1_1") (pintype "passive"))
      (node (ref "C33") (pin "1") (pinfunction "1_1") (pintype "passive"))
      (node (ref "C34") (pin "1") (pinfunction "1_1") (pintype "passive"))
      (node (ref "C35") (pin "1") (pinfunction "1_1") (pintype "passive"))
      (node (ref "C36") (pin "1") (pinfunction "1_1") (pintype "passive"))
      (node (ref "C37") (pin "1") (pinfunction "1_1") (pintype "passive"))
      (node (ref "C38") (pin "1") (pinfunction "1_1") (pintype "passive"))
      (node (ref "C39") (pin "1") (pinfunction "1_1") (pintype "passive"))
      (node (ref "C4") (pin "1") (pinfunction "1_1") (pintype "passive"))
      (node (ref "C40") (pin "1") (pinfunction "1_1") (pintype "passive"))
      (node (ref "C41") (pin "1") (pinfunction "1_1") (pintype "passive"))
      (node (ref "C42") (pin "1") (pinfunction "1_1") (pintype "passive"))
      (node (ref "C43") (pin "1") (pinfunction "1_1") (pintype "passive"))
      (node (ref "C44") (pin "1") (pinfunction "1_1") (pintype "passive"))
      (node (ref "C45") (pin "1") (pinfunction "1_1") (pintype "passive"))
      (node (ref "C46") (pin "1") (pinfunction "1_1") (pintype "passive"))
      (node (ref "C47") (pin "1") (pinfunction "1_1") (pintype "passive"))
      (node (ref "C48") (pin "1") (pinfunction "1_1") (pintype "passive"))
      (node (ref "C5") (pin "1") (pinfunction "1_1") (pintype "passive"))
      (node (ref "C51") (pin "+") (pinfunction "+_+") (pintype "passive"))
      (node (ref "C52") (pin "+") (pinfunction "+_+") (pintype "passive"))
      (node (ref "C53") (pin "+") (pinfunction "+_+") (pintype "passive"))
      (node (ref "C56") (pin "+") (pinfunction "+_+") (pintype "passive"))
      (node (ref "C57") (pin "1") (pinfunction "1_1") (pintype "passive"))
      (node (ref "C6") (pin "1") (pinfunction "1_1") (pintype "passive"))
      (node (ref "C7") (pin "1") (pinfunction "1_1") (pintype "passive"))
      (node (ref "C8") (pin "1") (pinfunction "1_1") (pintype "passive"))
      (node (ref "C9") (pin "1") (pinfunction "1_1") (pintype "passive"))
      (node (ref "IC3") (pin "4") (pinfunction "D0_4") (pintype "input"))
      (node (ref "IC4") (pin "4") (pinfunction "D0_4") (pintype "input"))
      (node (ref "OSC") (pin "8") (pinfunction "VCC_8") (pintype "power_in"))
      (node (ref "OSC1") (pin "14") (pinfunction "VCC_14") (pintype "power_in"))
      (node (ref "R1") (pin "2") (pinfunction "2_2") (pintype "passive"))
      (node (ref "R10") (pin "2") (pinfunction "2_2") (pintype "passive"))
      (node (ref "R15") (pin "2") (pinfunction "2_2") (pintype "passive"))
      (node (ref "R21") (pin "2") (pinfunction "2_2") (pintype "passive"))
      (node (ref "R24") (pin "2") (pinfunction "2_2") (pintype "passive"))
      (node (ref "R26") (pin "2") (pinfunction "2_2") (pintype "passive"))
      (node (ref "RN1") (pin "1") (pinfunction "1_1") (pintype "passive"))
      (node (ref "U$2") (pin "AA2") (pinfunction "1_AA2") (pintype "bidirectional"))
      (node (ref "U$2") (pin "BA2") (pinfunction "1_BA2") (pintype "bidirectional"))
      (node (ref "U$2") (pin "CA2") (pinfunction "1_CA2") (pintype "bidirectional"))
    )
    (net (code "182") (name "unconnected-(E3B-Q-Pad9)") (class "Default")
      (node (ref "E3") (pin "9") (pinfunction "Q_9") (pintype "output"))
    )
    (net (code "183") (name "unconnected-(E4A-Q-Pad5)") (class "Default")
      (node (ref "E4") (pin "5") (pinfunction "Q_5") (pintype "output"))
    )
    (net (code "184") (name "unconnected-(E4B-Q-Pad9)") (class "Default")
      (node (ref "E4") (pin "9") (pinfunction "Q_9") (pintype "output"))
    )
    (net (code "185") (name "unconnected-(E5A-QC-Pad8)") (class "Default")
      (node (ref "E5") (pin "8") (pinfunction "QC_8") (pintype "output"))
    )
    (net (code "186") (name "unconnected-(E6A-Q4-Pad12)") (class "Default")
      (node (ref "E6") (pin "12") (pinfunction "Q4_12") (pintype "output"))
    )
    (net (code "187") (name "unconnected-(E7B-~{Q}-Pad8)") (class "Default")
      (node (ref "E7") (pin "8") (pinfunction "~{Q}_8") (pintype "output"))
    )
    (net (code "188") (name "unconnected-(E16B-Q-Pad9)") (class "Default")
      (node (ref "E16") (pin "9") (pinfunction "Q_9") (pintype "output"))
    )
    (net (code "189") (name "unconnected-(E18A-QD-Pad11)") (class "Default")
      (node (ref "E18") (pin "11") (pinfunction "QD_11") (pintype "output"))
    )
    (net (code "190") (name "unconnected-(E20B-Q-Pad9)") (class "Default")
      (node (ref "E20") (pin "9") (pinfunction "Q_9") (pintype "output"))
    )
    (net (code "191") (name "unconnected-(E25A-I5-Pad12)") (class "Default")
      (node (ref "E25") (pin "12") (pinfunction "I5_12") (pintype "passive"))
    )
    (net (code "192") (name "unconnected-(E25A-I6-Pad11)") (class "Default")
      (node (ref "E25") (pin "11") (pinfunction "I6_11") (pintype "passive"))
    )
    (net (code "193") (name "unconnected-(E26A-I0-Pad3)") (class "Default")
      (node (ref "E26") (pin "3") (pinfunction "I0_3") (pintype "input"))
    )
    (net (code "194") (name "unconnected-(E26A-I1-Pad2)") (class "Default")
      (node (ref "E26") (pin "2") (pinfunction "I1_2") (pintype "input"))
    )
    (net (code "195") (name "unconnected-(E26A-I2-Pad15)") (class "Default")
      (node (ref "E26") (pin "15") (pinfunction "I2_15") (pintype "input"))
    )
    (net (code "196") (name "unconnected-(E26A-I3-Pad14)") (class "Default")
      (node (ref "E26") (pin "14") (pinfunction "I3_14") (pintype "input"))
    )
    (net (code "197") (name "unconnected-(E26A-Q1-Pad7)") (class "Default")
      (node (ref "E26") (pin "7") (pinfunction "Q1_7") (pintype "output"))
    )
    (net (code "198") (name "unconnected-(E26A-Q3-Pad11)") (class "Default")
      (node (ref "E26") (pin "11") (pinfunction "Q3_11") (pintype "output"))
    )
    (net (code "199") (name "unconnected-(E26A-Q4-Pad12)") (class "Default")
      (node (ref "E26") (pin "12") (pinfunction "Q4_12") (pintype "output"))
    )
    (net (code "200") (name "unconnected-(E28A-Q4-Pad12)") (class "Default")
      (node (ref "E28") (pin "12") (pinfunction "Q4_12") (pintype "output"))
    )
    (net (code "201") (name "unconnected-(E29A-Q-Pad5)") (class "Default")
      (node (ref "E29") (pin "5") (pinfunction "Q_5") (pintype "output"))
    )
    (net (code "202") (name "unconnected-(E29B-~{Q}-Pad8)") (class "Default")
      (node (ref "E29") (pin "8") (pinfunction "~{Q}_8") (pintype "output"))
    )
    (net (code "203") (name "unconnected-(E31A-Q4-Pad12)") (class "Default")
      (node (ref "E31") (pin "12") (pinfunction "Q4_12") (pintype "output"))
    )
    (net (code "204") (name "unconnected-(E38A-~{Q}-Pad6)") (class "Default")
      (node (ref "E38") (pin "6") (pinfunction "~{Q}_6") (pintype "output"))
    )
    (net (code "205") (name "unconnected-(E39A-I5-Pad12)") (class "Default")
      (node (ref "E39") (pin "12") (pinfunction "I5_12") (pintype "passive"))
    )
    (net (code "206") (name "unconnected-(E39A-I6-Pad11)") (class "Default")
      (node (ref "E39") (pin "11") (pinfunction "I6_11") (pintype "passive"))
    )
    (net (code "207") (name "unconnected-(E40A-3-Pad10)") (class "Default")
      (node (ref "E40") (pin "10") (pinfunction "3_10") (pintype "output"))
    )
    (net (code "208") (name "unconnected-(E40A-7-Pad5)") (class "Default")
      (node (ref "E40") (pin "5") (pinfunction "7_5") (pintype "output"))
    )
    (net (code "209") (name "unconnected-(E40A-8-Pad6)") (class "Default")
      (node (ref "E40") (pin "6") (pinfunction "8_6") (pintype "output"))
    )
    (net (code "210") (name "unconnected-(E40A-9-Pad7)") (class "Default")
      (node (ref "E40") (pin "7") (pinfunction "9_7") (pintype "output"))
    )
    (net (code "211") (name "unconnected-(E43A-3-Pad10)") (class "Default")
      (node (ref "E43") (pin "10") (pinfunction "3_10") (pintype "output"))
    )
    (net (code "212") (name "unconnected-(E43A-7-Pad5)") (class "Default")
      (node (ref "E43") (pin "5") (pinfunction "7_5") (pintype "output"))
    )
    (net (code "213") (name "unconnected-(E43A-8-Pad6)") (class "Default")
      (node (ref "E43") (pin "6") (pinfunction "8_6") (pintype "output"))
    )
    (net (code "214") (name "unconnected-(E43A-9-Pad7)") (class "Default")
      (node (ref "E43") (pin "7") (pinfunction "9_7") (pintype "output"))
    )
    (net (code "215") (name "unconnected-(E48A-Q-Pad5)") (class "Default")
      (node (ref "E48") (pin "5") (pinfunction "Q_5") (pintype "output"))
    )
    (net (code "216") (name "unconnected-(E48B-~{Q}-Pad8)") (class "Default")
      (node (ref "E48") (pin "8") (pinfunction "~{Q}_8") (pintype "output"))
    )
    (net (code "217") (name "unconnected-(IC1A-Y0-Pad15)") (class "Default")
      (node (ref "IC1") (pin "15") (pinfunction "Y0_15") (pintype "output"))
    )
    (net (code "218") (name "unconnected-(IC1A-Y1-Pad14)") (class "Default")
      (node (ref "IC1") (pin "14") (pinfunction "Y1_14") (pintype "output"))
    )
    (net (code "219") (name "unconnected-(IC1A-Y2-Pad13)") (class "Default")
      (node (ref "IC1") (pin "13") (pinfunction "Y2_13") (pintype "output"))
    )
    (net (code "220") (name "unconnected-(IC1A-Y5-Pad10)") (class "Default")
      (node (ref "IC1") (pin "10") (pinfunction "Y5_10") (pintype "output"))
    )
    (net (code "221") (name "unconnected-(IC3A-Y-Pad5)") (class "Default")
      (node (ref "IC3") (pin "5") (pinfunction "Y_5") (pintype "output"))
    )
    (net (code "222") (name "unconnected-(IC4A-Y-Pad5)") (class "Default")
      (node (ref "IC4") (pin "5") (pinfunction "Y_5") (pintype "output"))
    )
    (net (code "223") (name "unconnected-(IC5A-Y0-Pad15)") (class "Default")
      (node (ref "IC5") (pin "15") (pinfunction "Y0_15") (pintype "output"))
    )
    (net (code "224") (name "unconnected-(IC5A-Y1-Pad14)") (class "Default")
      (node (ref "IC5") (pin "14") (pinfunction "Y1_14") (pintype "output"))
    )
    (net (code "225") (name "unconnected-(IC5A-Y2-Pad13)") (class "Default")
      (node (ref "IC5") (pin "13") (pinfunction "Y2_13") (pintype "output"))
    )
    (net (code "226") (name "unconnected-(IC5A-Y5-Pad10)") (class "Default")
      (node (ref "IC5") (pin "10") (pinfunction "Y5_10") (pintype "output"))
    )
    (net (code "227") (name "unconnected-(IC5A-Y6-Pad9)") (class "Default")
      (node (ref "IC5") (pin "9") (pinfunction "Y6_9") (pintype "output"))
    )
    (net (code "228") (name "unconnected-(IC5A-Y7-Pad7)") (class "Default")
      (node (ref "IC5") (pin "7") (pinfunction "Y7_7") (pintype "output"))
    )
    (net (code "229") (name "unconnected-(IC6A-Y0-Pad15)") (class "Default")
      (node (ref "IC6") (pin "15") (pinfunction "Y0_15") (pintype "output"))
    )
    (net (code "230") (name "unconnected-(IC6A-Y1-Pad14)") (class "Default")
      (node (ref "IC6") (pin "14") (pinfunction "Y1_14") (pintype "output"))
    )
    (net (code "231") (name "unconnected-(IC6A-Y2-Pad13)") (class "Default")
      (node (ref "IC6") (pin "13") (pinfunction "Y2_13") (pintype "output"))
    )
    (net (code "232") (name "unconnected-(IC6A-Y3-Pad12)") (class "Default")
      (node (ref "IC6") (pin "12") (pinfunction "Y3_12") (pintype "output"))
    )
    (net (code "233") (name "unconnected-(IC6A-Y4-Pad11)") (class "Default")
      (node (ref "IC6") (pin "11") (pinfunction "Y4_11") (pintype "output"))
    )
    (net (code "234") (name "unconnected-(IC6A-Y7-Pad7)") (class "Default")
      (node (ref "IC6") (pin "7") (pinfunction "Y7_7") (pintype "output"))
    )
    (net (code "235") (name "unconnected-(IC7A-Y0-Pad15)") (class "Default")
      (node (ref "IC7") (pin "15") (pinfunction "Y0_15") (pintype "output"))
    )
    (net (code "236") (name "unconnected-(IC7A-Y1-Pad14)") (class "Default")
      (node (ref "IC7") (pin "14") (pinfunction "Y1_14") (pintype "output"))
    )
    (net (code "237") (name "unconnected-(IC7A-Y4-Pad11)") (class "Default")
      (node (ref "IC7") (pin "11") (pinfunction "Y4_11") (pintype "output"))
    )
    (net (code "238") (name "unconnected-(IC7A-Y5-Pad10)") (class "Default")
      (node (ref "IC7") (pin "10") (pinfunction "Y5_10") (pintype "output"))
    )
    (net (code "239") (name "unconnected-(IC7A-Y6-Pad9)") (class "Default")
      (node (ref "IC7") (pin "9") (pinfunction "Y6_9") (pintype "output"))
    )
    (net (code "240") (name "unconnected-(IC7A-Y7-Pad7)") (class "Default")
      (node (ref "IC7") (pin "7") (pinfunction "Y7_7") (pintype "output"))
    )
    (net (code "241") (name "unconnected-(RN1-Pad8)") (class "Default")
      (node (ref "RN1") (pin "8") (pinfunction "8_8") (pintype "passive"))
    )
    (net (code "242") (name "unconnected-(RN1-Pad9)") (class "Default")
      (node (ref "RN1") (pin "9") (pinfunction "9_9") (pintype "passive"))
    )
    (net (code "243") (name "unconnected-(RN1-Pad10)") (class "Default")
      (node (ref "RN1") (pin "10") (pinfunction "10_10") (pintype "passive"))
    )
    (net (code "244") (name "unconnected-(USB-Pad1)") (class "Default")
      (node (ref "USB") (pin "1") (pinfunction "1_1") (pintype "passive"))
    )
    (net (code "245") (name "unconnected-(USB-Pad4)") (class "Default")
      (node (ref "USB") (pin "4") (pinfunction "4_4") (pintype "passive"))
    )
    (net (code "246") (name "unconnected-(USB-Pad6)") (class "Default")
      (node (ref "USB") (pin "6") (pinfunction "6_6") (pintype "passive"))
    )
    (net (code "247") (name "unconnected-(USB-Pad7)") (class "Default")
      (node (ref "USB") (pin "7") (pinfunction "7_7") (pintype "passive"))
    )
    (net (code "248") (name "unconnected-(USB-Pad8)") (class "Default")
      (node (ref "USB") (pin "8") (pinfunction "8_8") (pintype "passive"))
    )
    (net (code "249") (name "unconnected-(USB-Pad9)") (class "Default")
      (node (ref "USB") (pin "9") (pinfunction "9_9") (pintype "passive"))
    )
    (net (code "250") (name "~{CKKCC}") (class "Default")
      (node (ref "E35") (pin "4") (pinfunction "I0_4") (pintype "input"))
      (node (ref "E44") (pin "11") (pinfunction "O_11") (pintype "output"))
      (node (ref "E48") (pin "13") (pinfunction "CLR_13") (pintype "input"))
    )
    (net (code "251") (name "~{CKTFL}") (class "Default")
      (node (ref "E38") (pin "1") (pinfunction "CLR_1") (pintype "input"))
      (node (ref "E42") (pin "2") (pinfunction "O_2") (pintype "output"))
    )
    (net (code "252") (name "~{DOTPC}") (class "Default")
      (node (ref "E27") (pin "10") (pinfunction "I1_10") (pintype "input"))
      (node (ref "E27") (pin "11") (pinfunction "I0_11") (pintype "input"))
      (node (ref "E27") (pin "5") (pinfunction "I1_5") (pintype "input"))
      (node (ref "E27") (pin "6") (pinfunction "I0_6") (pintype "input"))
      (node (ref "E28") (pin "13") (pinfunction "S_13") (pintype "input"))
      (node (ref "E30") (pin "10") (pinfunction "I1_10") (pintype "input"))
      (node (ref "E30") (pin "11") (pinfunction "I0_11") (pintype "input"))
      (node (ref "E30") (pin "5") (pinfunction "I1_5") (pintype "input"))
      (node (ref "E30") (pin "6") (pinfunction "I0_6") (pintype "input"))
      (node (ref "E31") (pin "13") (pinfunction "S_13") (pintype "input"))
      (node (ref "E35") (pin "3") (pinfunction "O_3") (pintype "output"))
      (node (ref "R10") (pin "1") (pinfunction "1_1") (pintype "passive"))
    )
    (net (code "253") (name "~{INIT}") (class "Default")
      (node (ref "E16") (pin "13") (pinfunction "CLR_13") (pintype "input"))
      (node (ref "E16") (pin "4") (pinfunction "PRE_4") (pintype "input"))
      (node (ref "E29") (pin "13") (pinfunction "CLR_13") (pintype "input"))
      (node (ref "E46") (pin "13") (pinfunction "O_13") (pintype "output"))
      (node (ref "E48") (pin "10") (pinfunction "PRE_10") (pintype "input"))
    )
    (net (code "254") (name "~{INT_ENAB}") (class "Default")
      (node (ref "E38") (pin "9") (pinfunction "Q_9") (pintype "output"))
      (node (ref "E45") (pin "9") (pinfunction "I1_9") (pintype "input"))
    )
    (net (code "255") (name "~{KCC}") (class "Default")
      (node (ref "E43") (pin "11") (pinfunction "2_11") (pintype "output"))
      (node (ref "E44") (pin "10") (pinfunction "I1_10") (pintype "input"))
    )
    (net (code "256") (name "~{KCF}") (class "Default")
      (node (ref "E43") (pin "13") (pinfunction "0_13") (pintype "output"))
      (node (ref "E47") (pin "6") (pinfunction "I1_6") (pintype "input"))
    )
    (net (code "257") (name "~{KIE}") (class "Default")
      (node (ref "E43") (pin "3") (pinfunction "5_3") (pintype "output"))
      (node (ref "E47") (pin "8") (pinfunction "I0_8") (pintype "input"))
    )
    (net (code "258") (name "~{KRB}") (class "Default")
      (node (ref "E43") (pin "4") (pinfunction "6_4") (pintype "output"))
      (node (ref "E44") (pin "4") (pinfunction "I0_4") (pintype "input"))
      (node (ref "E44") (pin "9") (pinfunction "I0_9") (pintype "input"))
    )
    (net (code "259") (name "~{KRS}") (class "Default")
      (node (ref "E43") (pin "9") (pinfunction "4_9") (pintype "output"))
      (node (ref "E44") (pin "5") (pinfunction "I1_5") (pintype "input"))
    )
    (net (code "260") (name "~{KSF}") (class "Default")
      (node (ref "E43") (pin "12") (pinfunction "1_12") (pintype "output"))
      (node (ref "E47") (pin "11") (pinfunction "I0_11") (pintype "input"))
    )
    (net (code "261") (name "~{LAST_UNIT}") (class "Default")
      (node (ref "E12") (pin "12") (pinfunction "I0_12") (pintype "input"))
      (node (ref "E8") (pin "6") (pinfunction "~{Q}_6") (pintype "output"))
    )
    (net (code "262") (name "~{P_PULSE}") (class "Default")
      (node (ref "E10") (pin "13") (pinfunction "S_13") (pintype "input"))
      (node (ref "E11") (pin "8") (pinfunction "I0_8") (pintype "input"))
      (node (ref "E6") (pin "13") (pinfunction "S_13") (pintype "input"))
      (node (ref "E7") (pin "9") (pinfunction "Q_9") (pintype "output"))
    )
    (net (code "263") (name "~{RFLG}") (class "Default")
      (node (ref "E44") (pin "1") (pinfunction "I0_1") (pintype "input"))
      (node (ref "E47") (pin "12") (pinfunction "I1_12") (pintype "input"))
      (node (ref "E48") (pin "6") (pinfunction "~{Q}_6") (pintype "output"))
    )
    (net (code "264") (name "~{RX_ACTIVE8}") (class "Default")
      (node (ref "E11") (pin "11") (pinfunction "I0_11") (pintype "input"))
      (node (ref "E11") (pin "12") (pinfunction "I1_12") (pintype "input"))
      (node (ref "E12") (pin "3") (pinfunction "O_3") (pintype "output"))
      (node (ref "E16") (pin "11") (pinfunction "CLK_11") (pintype "input"))
      (node (ref "E39") (pin "1") (pinfunction "I4_1") (pintype "input"))
    )
    (net (code "265") (name "~{RX_ACTIVE}") (class "Default")
      (node (ref "E12") (pin "13") (pinfunction "I1_13") (pintype "input"))
      (node (ref "E12") (pin "4") (pinfunction "I0_4") (pintype "input"))
      (node (ref "E7") (pin "6") (pinfunction "~{Q}_6") (pintype "output"))
    )
    (net (code "266") (name "~{RX_AGAIN}") (class "Default")
      (node (ref "E16") (pin "10") (pinfunction "PRE_10") (pintype "input"))
      (node (ref "E19") (pin "12") (pinfunction "O_12") (pintype "output"))
      (node (ref "E7") (pin "4") (pinfunction "PRE_4") (pintype "input"))
    )
    (net (code "267") (name "~{RX_DIV2}") (class "Default")
      (node (ref "E11") (pin "9") (pinfunction "I1_9") (pintype "input"))
      (node (ref "E4") (pin "11") (pinfunction "CLK_11") (pintype "input"))
      (node (ref "E4") (pin "2") (pinfunction "D_2") (pintype "input"))
      (node (ref "E4") (pin "6") (pinfunction "~{Q}_6") (pintype "output"))
    )
    (net (code "268") (name "~{RX_DIV4}") (class "Default")
      (node (ref "E4") (pin "12") (pinfunction "D_12") (pintype "input"))
      (node (ref "E4") (pin "8") (pinfunction "~{Q}_8") (pintype "output"))
      (node (ref "E7") (pin "10") (pinfunction "PRE_10") (pintype "input"))
      (node (ref "E8") (pin "11") (pinfunction "CLK_11") (pintype "input"))
    )
    (net (code "269") (name "~{RX_DIV}") (class "Default")
      (node (ref "E3") (pin "6") (pinfunction "~{Q}_6") (pintype "output"))
      (node (ref "E4") (pin "3") (pinfunction "CLK_3") (pintype "input"))
    )
    (net (code "270") (name "~{RX_LAST}") (class "Default")
      (node (ref "E12") (pin "10") (pinfunction "I1_10") (pintype "input"))
      (node (ref "E12") (pin "11") (pinfunction "O_11") (pintype "output"))
      (node (ref "E21") (pin "11") (pinfunction "I_11") (pintype "input"))
      (node (ref "E36") (pin "4") (pinfunction "I0_4") (pintype "input"))
      (node (ref "E36") (pin "5") (pinfunction "I1_5") (pintype "input"))
      (node (ref "R15") (pin "1") (pinfunction "1_1") (pintype "passive"))
    )
    (net (code "271") (name "~{R_RUN}") (class "Default")
      (node (ref "E48") (pin "9") (pinfunction "Q_9") (pintype "output"))
      (node (ref "U$2") (pin "DB1") (pinfunction "1_DB1") (pintype "bidirectional"))
    )
    (net (code "272") (name "~{SPIKE_DET}") (class "Default")
      (node (ref "E11") (pin "2") (pinfunction "I0_2") (pintype "input"))
      (node (ref "E16") (pin "8") (pinfunction "~{Q}_8") (pintype "output"))
    )
    (net (code "273") (name "~{START}") (class "Default")
      (node (ref "E20") (pin "8") (pinfunction "~{Q}_8") (pintype "output"))
      (node (ref "E29") (pin "1") (pinfunction "CLR_1") (pintype "input"))
    )
    (net (code "274") (name "~{TCF}") (class "Default")
      (node (ref "E40") (pin "11") (pinfunction "2_11") (pintype "output"))
      (node (ref "E41") (pin "10") (pinfunction "I1_10") (pintype "input"))
    )
    (net (code "275") (name "~{TFLG}") (class "Default")
      (node (ref "E38") (pin "5") (pinfunction "Q_5") (pintype "output"))
      (node (ref "E44") (pin "2") (pinfunction "I1_2") (pintype "input"))
      (node (ref "E45") (pin "11") (pinfunction "I0_11") (pintype "input"))
    )
    (net (code "276") (name "~{TFL}") (class "Default")
      (node (ref "E40") (pin "13") (pinfunction "0_13") (pintype "output"))
      (node (ref "E45") (pin "2") (pinfunction "I0_2") (pintype "input"))
    )
    (net (code "277") (name "~{TLS}") (class "Default")
      (node (ref "E40") (pin "4") (pinfunction "6_4") (pintype "output"))
      (node (ref "E41") (pin "4") (pinfunction "I0_4") (pintype "input"))
      (node (ref "E41") (pin "9") (pinfunction "I0_9") (pintype "input"))
    )
    (net (code "278") (name "~{TP3}") (class "Default")
      (node (ref "E42") (pin "4") (pinfunction "O_4") (pintype "output"))
      (node (ref "E45") (pin "3") (pinfunction "I1_3") (pintype "input"))
      (node (ref "E47") (pin "5") (pinfunction "I0_5") (pintype "input"))
      (node (ref "E47") (pin "9") (pinfunction "I1_9") (pintype "input"))
    )
    (net (code "279") (name "~{TPC}") (class "Default")
      (node (ref "E40") (pin "9") (pinfunction "4_9") (pintype "output"))
      (node (ref "E41") (pin "5") (pinfunction "I1_5") (pintype "input"))
    )
    (net (code "280") (name "~{TSF}") (class "Default")
      (node (ref "E40") (pin "12") (pinfunction "1_12") (pintype "output"))
      (node (ref "E45") (pin "12") (pinfunction "I1_12") (pintype "input"))
    )
    (net (code "281") (name "~{TSK}") (class "Default")
      (node (ref "E40") (pin "3") (pinfunction "5_3") (pintype "output"))
      (node (ref "E45") (pin "8") (pinfunction "I0_8") (pintype "input"))
    )
    (net (code "282") (name "~{TX_ACTIVE}") (class "Default")
      (node (ref "E20") (pin "5") (pinfunction "Q_5") (pintype "output"))
      (node (ref "E26") (pin "4") (pinfunction "D_4") (pintype "input"))
    )
    (net (code "283") (name "~{TX_DIV}") (class "Default")
      (node (ref "DL1") (pin "1") (pinfunction "1_1") (pintype "passive"))
      (node (ref "E16") (pin "6") (pinfunction "~{Q}_6") (pintype "output"))
      (node (ref "E19") (pin "4") (pinfunction "I1_4") (pintype "input"))
      (node (ref "R21") (pin "1") (pinfunction "1_1") (pintype "passive"))
    )
    (net (code "284") (name "~{TX_SHIFT}") (class "Default")
      (node (ref "E21") (pin "3") (pinfunction "I_3") (pintype "input"))
      (node (ref "E25") (pin "6") (pinfunction "O_6") (pintype "output"))
      (node (ref "E28") (pin "6") (pinfunction "C_6") (pintype "input"))
      (node (ref "E31") (pin "6") (pinfunction "C_6") (pintype "input"))
    )
  )
)
